# measurement_rev4.net
KiCad netlist of a schematic drawn in Altium Designer
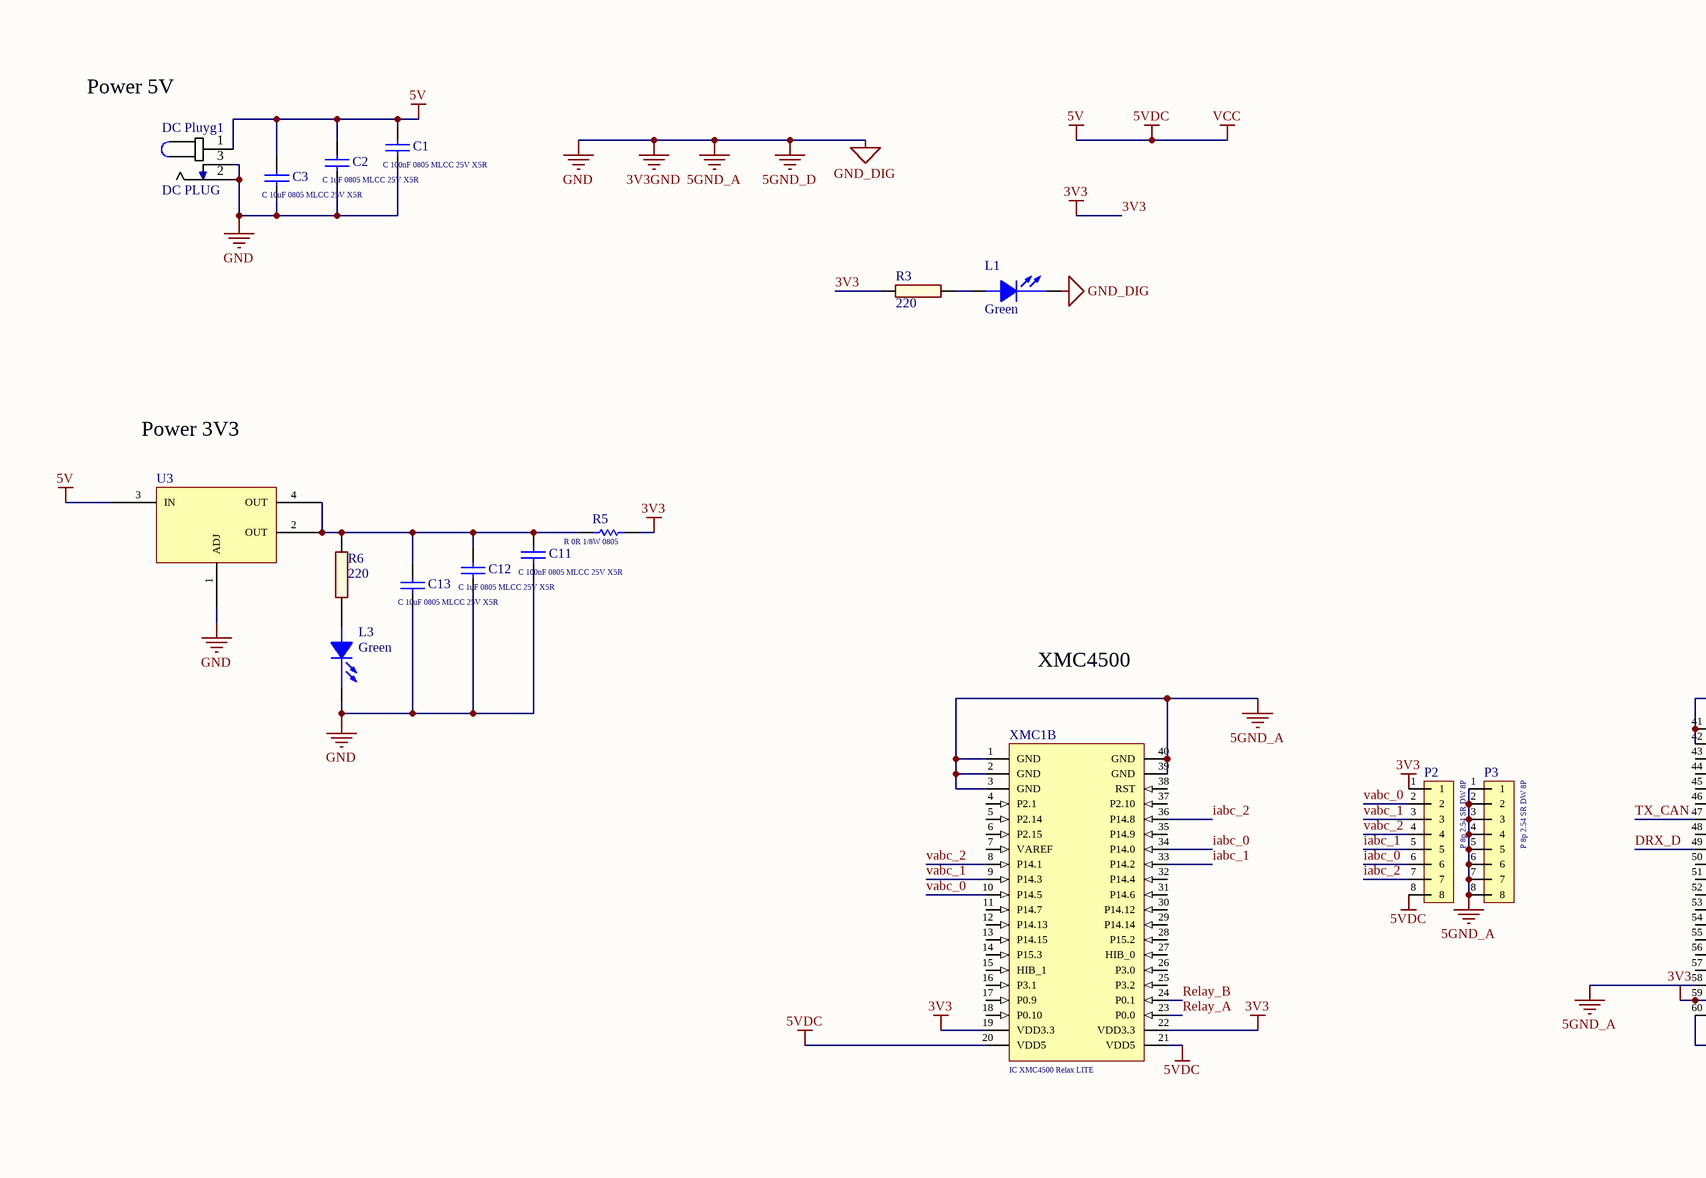
[diagram p0: measurement_rev4.SchDoc, top left]
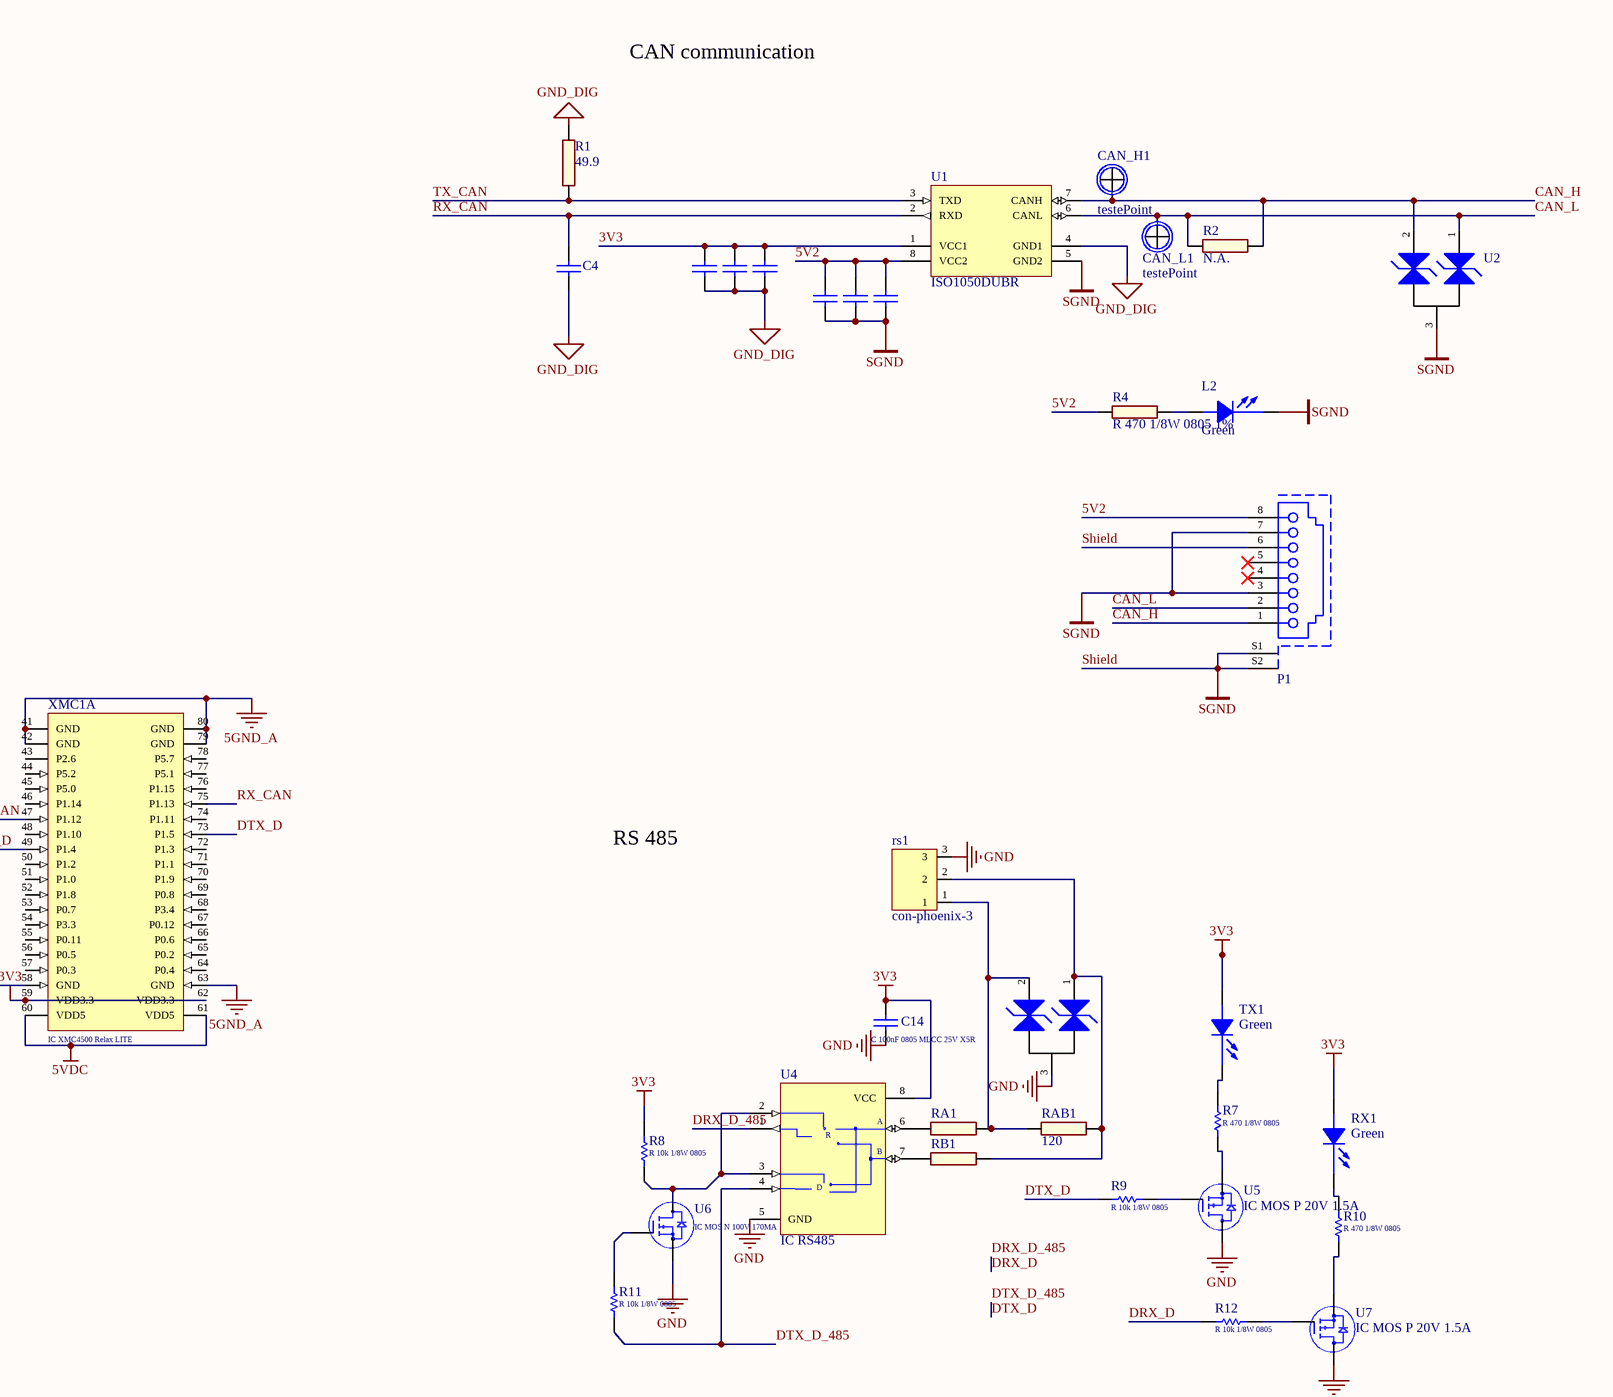
[diagram p1: measurement_rev4.SchDoc, top right]
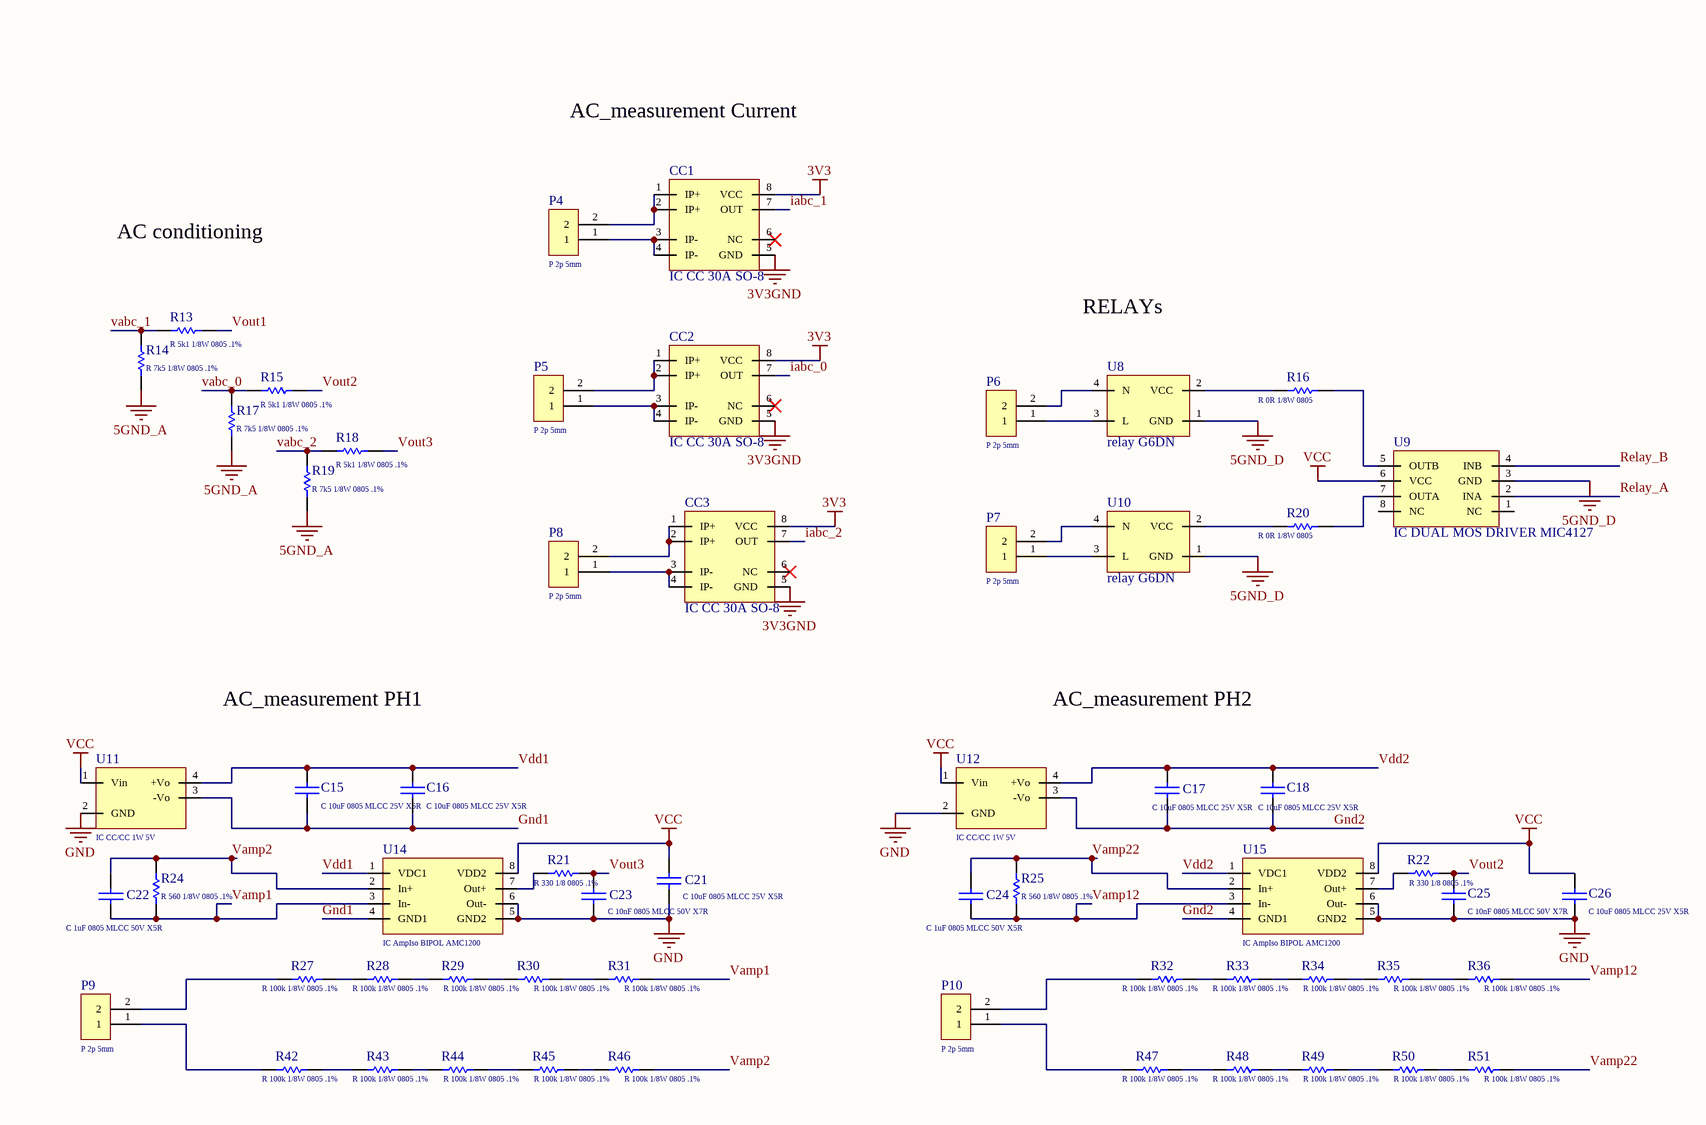
[diagram p2: measurement_rev4.SchDoc, bottom left]
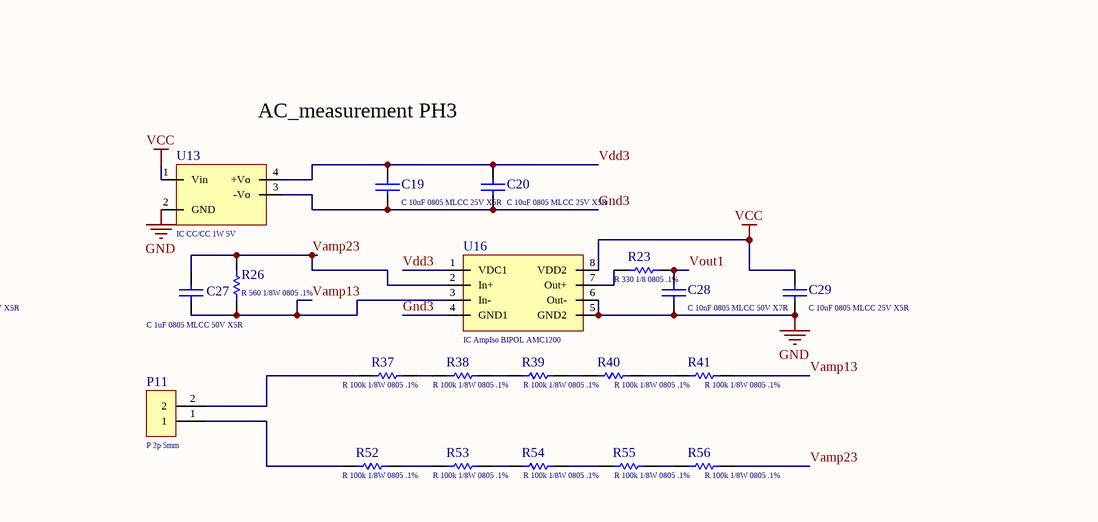
[diagram p3: measurement_rev4.SchDoc, bottom right]

(export (version "E")
  (design (tool "Eeschema 10.0.6"))
  (components
    (comp (ref "C1")
      (value "C 100nF 0805 MLCC 25V X5R")
      (footprint "CAPC_0805")
      (description "MULTILAYER CERAMIC CAPACITORS MLCC - SMD/SMT 100NF 50V 0805 ROHS")
      (fields (field (name "LCSC PART #") "C49678"))
      (libsource (lib "vi_measurement") (part "Capacitor SMD"))
    )
    (comp (ref "C2")
      (value "C 1uF 0805 MLCC 25V X5R")
      (footprint "CAPC_0805")
      (description "MULTILAYER CERAMIC CAPACITORS MLCC - SMD/SMT 1UF 50V 0805 ROHS")
      (fields (field (name "LCSC PART #") "C28323"))
      (libsource (lib "vi_measurement") (part "Capacitor SMD"))
    )
    (comp (ref "C3")
      (value "C 10uF 0805 MLCC 25V X5R")
      (footprint "CAPC_0805")
      (description "Capacitores de cerâmica multicamada MLCC - SMD/SMT 10uF 25V X5R +/-10% 0805 Gen Purp")
      (fields (field (name "LCSC PART #") "C15850"))
      (libsource (lib "vi_measurement") (part "Capacitor SMD"))
    )
    (comp (ref "C4")
      (value "Capacitor")
      (footprint "CAPC_0805")
      (fields (field (name "LCSC PART #") "C1794"))
      (libsource (lib "myLibraryAltium") (part "Capacitor"))
    )
    (comp (ref "C5")
      (value "Capacitor")
      (footprint "CAPC_0805")
      (fields (field (name "LCSC PART #") "C28323"))
      (libsource (lib "myLibraryAltium") (part "Capacitor"))
    )
    (comp (ref "C6")
      (value "Capacitor")
      (footprint "CAPC_0805")
      (fields (field (name "LCSC PART #") "C49678"))
      (libsource (lib "myLibraryAltium") (part "Capacitor"))
    )
    (comp (ref "C7")
      (value "Capacitor")
      (footprint "CAPC_0805")
      (fields (field (name "LCSC PART #") "C1710"))
      (libsource (lib "myLibraryAltium") (part "Capacitor"))
    )
    (comp (ref "C8")
      (value "Capacitor")
      (footprint "CAPC_0805")
      (fields (field (name "LCSC PART #") "C28323"))
      (libsource (lib "myLibraryAltium") (part "Capacitor"))
    )
    (comp (ref "C9")
      (value "Capacitor")
      (footprint "CAPC_0805")
      (fields (field (name "LCSC PART #") "C49678"))
      (libsource (lib "myLibraryAltium") (part "Capacitor"))
    )
    (comp (ref "C10")
      (value "Capacitor")
      (footprint "CAPC_0805")
      (fields (field (name "LCSC PART #") "C1710"))
      (libsource (lib "myLibraryAltium") (part "Capacitor"))
    )
    (comp (ref "C11")
      (value "C 100nF 0805 MLCC 25V X5R")
      (footprint "CAPC_0805")
      (description "MULTILAYER CERAMIC CAPACITORS MLCC - SMD/SMT 100NF 50V 0805 ROHS")
      (fields (field (name "LCSC PART #") "C49678"))
      (libsource (lib "vi_measurement") (part "Capacitor SMD"))
    )
    (comp (ref "C12")
      (value "C 1uF 0805 MLCC 25V X5R")
      (footprint "CAPC_0805")
      (description "MULTILAYER CERAMIC CAPACITORS MLCC - SMD/SMT 1UF 50V 0805 ROHS")
      (fields (field (name "LCSC PART #") "C28323"))
      (libsource (lib "vi_measurement") (part "Capacitor SMD"))
    )
    (comp (ref "C13")
      (value "C 10uF 0805 MLCC 25V X5R")
      (footprint "CAPC_0805")
      (description "Capacitores de cerâmica multicamada MLCC - SMD/SMT 10uF 25V X5R +/-10% 0805 Gen Purp")
      (fields (field (name "LCSC PART #") "C15850"))
      (libsource (lib "vi_measurement") (part "Capacitor SMD"))
    )
    (comp (ref "C14")
      (value "C 100nF 0805 MLCC 25V X5R")
      (footprint "CAPC_0805")
      (description "MULTILAYER CERAMIC CAPACITORS MLCC - SMD/SMT 100NF 50V 0805 ROHS")
      (fields (field (name "LCSC PART #") "C49678"))
      (libsource (lib "vi_measurement") (part "Capacitor SMD"))
    )
    (comp (ref "C15")
      (value "C 10uF 0805 MLCC 25V X5R")
      (footprint "CAPC_0805")
      (description "Capacitores de cerâmica multicamada MLCC - SMD/SMT 10uF 25V X5R +/-10% 0805 Gen Purp")
      (fields (field (name "LCSC PART #") "C15850"))
      (libsource (lib "vi_measurement") (part "Capacitor SMD"))
    )
    (comp (ref "C16")
      (value "C 10uF 0805 MLCC 25V X5R")
      (footprint "CAPC_0805")
      (description "Capacitores de cerâmica multicamada MLCC - SMD/SMT 10uF 25V X5R +/-10% 0805 Gen Purp")
      (fields (field (name "LCSC PART #") "C15850"))
      (libsource (lib "vi_measurement") (part "Capacitor SMD"))
    )
    (comp (ref "C17")
      (value "C 10uF 0805 MLCC 25V X5R")
      (footprint "CAPC_0805")
      (description "Capacitores de cerâmica multicamada MLCC - SMD/SMT 10uF 25V X5R +/-10% 0805 Gen Purp")
      (fields (field (name "LCSC PART #") "C15850"))
      (libsource (lib "vi_measurement") (part "Capacitor SMD"))
    )
    (comp (ref "C18")
      (value "C 10uF 0805 MLCC 25V X5R")
      (footprint "CAPC_0805")
      (description "Capacitores de cerâmica multicamada MLCC - SMD/SMT 10uF 25V X5R +/-10% 0805 Gen Purp")
      (fields (field (name "LCSC PART #") "C15850"))
      (libsource (lib "vi_measurement") (part "Capacitor SMD"))
    )
    (comp (ref "C19")
      (value "C 10uF 0805 MLCC 25V X5R")
      (footprint "CAPC_0805")
      (description "Capacitores de cerâmica multicamada MLCC - SMD/SMT 10uF 25V X5R +/-10% 0805 Gen Purp")
      (fields (field (name "LCSC PART #") "C15850"))
      (libsource (lib "vi_measurement") (part "Capacitor SMD"))
    )
    (comp (ref "C20")
      (value "C 10uF 0805 MLCC 25V X5R")
      (footprint "CAPC_0805")
      (description "Capacitores de cerâmica multicamada MLCC - SMD/SMT 10uF 25V X5R +/-10% 0805 Gen Purp")
      (fields (field (name "LCSC PART #") "C15850"))
      (libsource (lib "vi_measurement") (part "Capacitor SMD"))
    )
    (comp (ref "C21")
      (value "C 10uF 0805 MLCC 25V X5R")
      (footprint "CAPC_0805")
      (description "Capacitores de cerâmica multicamada MLCC - SMD/SMT 10uF 25V X5R +/-10% 0805 Gen Purp")
      (fields (field (name "LCSC PART #") "C15850"))
      (libsource (lib "vi_measurement") (part "Capacitor SMD"))
    )
    (comp (ref "C22")
      (value "C 1uF 0805 MLCC 50V X5R")
      (footprint "CAPC_0805")
      (description "Capacitores de cerâmica multicamada MLCC - SMD/SMT 0805 50V 1uF 20% X5R")
      (fields (field (name "LCSC PART #") "C28323"))
      (libsource (lib "vi_measurement") (part "Capacitor SMD"))
    )
    (comp (ref "C23")
      (value "C 10nF 0805 MLCC 50V X7R")
      (footprint "CAPC_0805")
      (description "Capacitores de cerâmica multicamada MLCC - SMD/SMT 10nF 50V X7R 10%")
      (fields (field (name "LCSC PART #") "C1710"))
      (libsource (lib "vi_measurement") (part "Capacitor SMD"))
    )
    (comp (ref "C24")
      (value "C 1uF 0805 MLCC 50V X5R")
      (footprint "CAPC_0805")
      (description "Capacitores de cerâmica multicamada MLCC - SMD/SMT 0805 50V 1uF 20% X5R")
      (fields (field (name "LCSC PART #") "C28323"))
      (libsource (lib "vi_measurement") (part "Capacitor SMD"))
    )
    (comp (ref "C25")
      (value "C 10nF 0805 MLCC 50V X7R")
      (footprint "CAPC_0805")
      (description "Capacitores de cerâmica multicamada MLCC - SMD/SMT 10nF 50V X7R 10%")
      (fields (field (name "LCSC PART #") "C1710"))
      (libsource (lib "vi_measurement") (part "Capacitor SMD"))
    )
    (comp (ref "C26")
      (value "C 10uF 0805 MLCC 25V X5R")
      (footprint "CAPC_0805")
      (description "Capacitores de cerâmica multicamada MLCC - SMD/SMT 10uF 25V X5R +/-10% 0805 Gen Purp")
      (fields (field (name "LCSC PART #") "C15850"))
      (libsource (lib "vi_measurement") (part "Capacitor SMD"))
    )
    (comp (ref "C27")
      (value "C 1uF 0805 MLCC 50V X5R")
      (footprint "CAPC_0805")
      (description "Capacitores de cerâmica multicamada MLCC - SMD/SMT 0805 50V 1uF 20% X5R")
      (fields (field (name "LCSC PART #") "C28323"))
      (libsource (lib "vi_measurement") (part "Capacitor SMD"))
    )
    (comp (ref "C28")
      (value "C 10nF 0805 MLCC 50V X7R")
      (footprint "CAPC_0805")
      (description "Capacitores de cerâmica multicamada MLCC - SMD/SMT 10nF 50V X7R 10%")
      (fields (field (name "LCSC PART #") "C1710"))
      (libsource (lib "vi_measurement") (part "Capacitor SMD"))
    )
    (comp (ref "C29")
      (value "C 10uF 0805 MLCC 25V X5R")
      (footprint "CAPC_0805")
      (description "Capacitores de cerâmica multicamada MLCC - SMD/SMT 10uF 25V X5R +/-10% 0805 Gen Purp")
      (fields (field (name "LCSC PART #") "C15850"))
      (libsource (lib "vi_measurement") (part "Capacitor SMD"))
    )
    (comp (ref "CAN_H1")
      (value "testePoint")
      (footprint "PAD 2.5MM - FURO 1.25MM")
      (libsource (lib "myLibraryAltium") (part "testePoint"))
    )
    (comp (ref "CAN_L1")
      (value "testePoint")
      (footprint "PAD 2.5MM - FURO 1.25MM")
      (libsource (lib "myLibraryAltium") (part "testePoint"))
    )
    (comp (ref "CC1")
      (value "IC CC 30A SO-8")
      (footprint "CC6303_SOP8")
      (description "Sensores de Corrente de Montagem de Painel Hall Effect IC LF 30A 66 mV/A")
      (fields (field (name "LCSC PART #") "C163283"))
      (libsource (lib "vmorais_libraries") (part "Current_Sensor_cc6303"))
    )
    (comp (ref "CC2")
      (value "IC CC 30A SO-8")
      (footprint "CC6303_SOP8")
      (description "Sensores de Corrente de Montagem de Painel Hall Effect IC LF 30A 66 mV/A")
      (fields (field (name "LCSC PART #") "C163283"))
      (libsource (lib "vmorais_libraries") (part "Current_Sensor_cc6303"))
    )
    (comp (ref "CC3")
      (value "IC CC 30A SO-8")
      (footprint "CC6303_SOP8")
      (description "Sensores de Corrente de Montagem de Painel Hall Effect IC LF 30A 66 mV/A")
      (fields (field (name "LCSC PART #") "C163283"))
      (libsource (lib "vmorais_libraries") (part "Current_Sensor_cc6303"))
    )
    (comp (ref "DC Pluyg1")
      (value "DC PLUG")
      (footprint "DC Plug")
      (libsource (lib "myLibraryAltium") (part "DC PLUG"))
    )
    (comp (ref "L1")
      (value "Green")
      (footprint "CD2012-0805")
      (description "LED 2X1.2MM 570NM GN WTR CLR SMD")
      (fields (field (name "MANUFACTURER") "Kingbright") (field (name "MPN") "APT2012CGCK"))
      (libsource (lib "myLibraryAltium") (part "LED_GREEN"))
    )
    (comp (ref "L2")
      (value "Green")
      (footprint "CD2012-0805")
      (description "LED 2X1.2MM 570NM GN WTR CLR SMD")
      (fields (field (name "MANUFACTURER") "Kingbright") (field (name "MPN") "APT2012CGCK"))
      (libsource (lib "myLibraryAltium") (part "LED_GREEN"))
    )
    (comp (ref "L3")
      (value "Green")
      (footprint "CD2012-0805")
      (description "LED 2X1.2MM 570NM GN WTR CLR SMD")
      (fields (field (name "MANUFACTURER") "Kingbright") (field (name "MPN") "APT2012CGCK"))
      (libsource (lib "myLibraryAltium") (part "LED_GREEN"))
    )
    (comp (ref "P1")
      (value "61500814221")
      (footprint "61500814221")
      (description "Modular Jack Horizontal Shielded 8P8C Tab Down WR-MJ")
      (fields (field (name "PUBLISHER") "Wurth Elektronik"))
      (libsource (lib "Modular Jack Connector_WR-MJ") (part "61500814221"))
    )
    (comp (ref "P2")
      (value "P 8p 2.54 SR DW 8P")
      (footprint "Header 8x1 8.5mm")
      (description "Distribuidores e Alojamento de Fios CGrid Hrd SRDW THo le 8ckt")
      (libsource (lib "vmorais_libraries") (part "jumper_8p"))
    )
    (comp (ref "P3")
      (value "P 8p 2.54 SR DW 8P")
      (footprint "Header 8x1 8.5mm")
      (description "Distribuidores e Alojamento de Fios CGrid Hrd SRDW THo le 8ckt")
      (libsource (lib "vmorais_libraries") (part "jumper_8p"))
    )
    (comp (ref "P4")
      (value "P 2p 5mm")
      (footprint "connector1x2_parafuso")
      (description "Bloques de terminales de PCB de perfil estándar RS de 5,0 mm")
      (libsource (lib "malvega_pcb") (part "gen_purpose_conn_1x2"))
    )
    (comp (ref "P5")
      (value "P 2p 5mm")
      (footprint "connector1x2_parafuso")
      (description "Bloques de terminales de PCB de perfil estándar RS de 5,0 mm")
      (libsource (lib "malvega_pcb") (part "gen_purpose_conn_1x2"))
    )
    (comp (ref "P6")
      (value "P 2p 5mm")
      (footprint "connector1x2_parafuso")
      (description "Bloques de terminales de PCB de perfil estándar RS de 5,0 mm")
      (libsource (lib "malvega_pcb") (part "gen_purpose_conn_1x2"))
    )
    (comp (ref "P7")
      (value "P 2p 5mm")
      (footprint "connector1x2_parafuso")
      (description "Bloques de terminales de PCB de perfil estándar RS de 5,0 mm")
      (libsource (lib "malvega_pcb") (part "gen_purpose_conn_1x2"))
    )
    (comp (ref "P8")
      (value "P 2p 5mm")
      (footprint "connector1x2_parafuso")
      (description "Bloques de terminales de PCB de perfil estándar RS de 5,0 mm")
      (libsource (lib "malvega_pcb") (part "gen_purpose_conn_1x2"))
    )
    (comp (ref "P9")
      (value "P 2p 5mm")
      (footprint "connector1x2_parafuso")
      (description "Bloques de terminales de PCB de perfil estándar RS de 5,0 mm")
      (libsource (lib "malvega_pcb") (part "gen_purpose_conn_1x2"))
    )
    (comp (ref "P10")
      (value "P 2p 5mm")
      (footprint "connector1x2_parafuso")
      (description "Bloques de terminales de PCB de perfil estándar RS de 5,0 mm")
      (libsource (lib "malvega_pcb") (part "gen_purpose_conn_1x2"))
    )
    (comp (ref "P11")
      (value "P 2p 5mm")
      (footprint "connector1x2_parafuso")
      (description "Bloques de terminales de PCB de perfil estándar RS de 5,0 mm")
      (libsource (lib "malvega_pcb") (part "gen_purpose_conn_1x2"))
    )
    (comp (ref "R1")
      (value "49.9")
      (footprint "RESC_0805")
      (description "Thick film resistor, SMD 0402, 1/16W, 1%")
      (fields (field (name "MANUFACTURER") "Generic") (field (name "LCSC PART #") "C17720"))
      (libsource (lib "") (part "R2_1"))
    )
    (comp (ref "R2")
      (value "N.A.")
      (footprint "RESC_0805")
      (description "Thick film resistor, SMD 0402, 1/16W, 1%")
      (fields (field (name "MANUFACTURER") "Generic"))
      (libsource (lib "myLibraryAltium") (part "R2"))
    )
    (comp (ref "R3")
      (value "220")
      (footprint "RESC_0805")
      (description "Thick film resistor, SMD 0402, 1/16W, 1%")
      (fields (field (name "MANUFACTURER") "Generic") (field (name "LCSC PART #") "C17557"))
      (libsource (lib "") (part "R2_2"))
    )
    (comp (ref "R4")
      (value "R 470 1/8W 0805 1%")
      (footprint "RESC_0805")
      (description "Resistores de Filme Espesso - SMD 1/8Watt 470ohms 1% Commercial Use")
      (fields (field (name "MANUFACTURER") "Generic") (field (name "LCSC PART #") "C17710"))
      (libsource (lib "") (part "R2_2"))
    )
    (comp (ref "R5")
      (value "R 0R 1/8W 0805")
      (footprint "RESC_0805")
      (description "Resistores de Filme Fino - SMD 0 ohm")
      (fields (field (name "LCSC PART #") "C17477"))
      (libsource (lib "inversor_50a") (part "Resistor"))
    )
    (comp (ref "R6")
      (value "220")
      (footprint "RESC_0805")
      (description "Thick film resistor, SMD 0402, 1/16W, 1%")
      (fields (field (name "MANUFACTURER") "Generic") (field (name "LCSC PART #") "C17557"))
      (libsource (lib "") (part "R2_1"))
    )
    (comp (ref "R7")
      (value "R 470 1/8W 0805")
      (footprint "RESC_0805")
      (description "CHIP RESISTOR - SURFACE MOUNT 470OHMS ±1% 1/8W 0805 ROHS")
      (fields (field (name "LCSC PART #") "C17710"))
      (libsource (lib "inversor_50a") (part "Resistor"))
    )
    (comp (ref "R8")
      (value "R 10k 1/8W 0805")
      (footprint "RESC_0805")
      (description "CHIP RESISTOR - SURFACE MOUNT 10KOHMS ±1% 1/8W 0805 ROHS")
      (fields (field (name "LCSC PART #") "C17414"))
      (libsource (lib "inversor_50a") (part "Resistor"))
    )
    (comp (ref "R9")
      (value "R 10k 1/8W 0805")
      (footprint "RESC_0805")
      (description "CHIP RESISTOR - SURFACE MOUNT 10KOHMS ±1% 1/8W 0805 ROHS")
      (fields (field (name "LCSC PART #") "C17414"))
      (libsource (lib "inversor_50a") (part "Resistor"))
    )
    (comp (ref "R10")
      (value "R 470 1/8W 0805")
      (footprint "RESC_0805")
      (description "CHIP RESISTOR - SURFACE MOUNT 470OHMS ±1% 1/8W 0805 ROHS")
      (fields (field (name "LCSC PART #") "C17710"))
      (libsource (lib "inversor_50a") (part "Resistor"))
    )
    (comp (ref "R11")
      (value "R 10k 1/8W 0805")
      (footprint "RESC_0805")
      (description "CHIP RESISTOR - SURFACE MOUNT 10KOHMS ±1% 1/8W 0805 ROHS")
      (fields (field (name "LCSC PART #") "C17414"))
      (libsource (lib "inversor_50a") (part "Resistor"))
    )
    (comp (ref "R12")
      (value "R 10k 1/8W 0805")
      (footprint "RESC_0805")
      (description "CHIP RESISTOR - SURFACE MOUNT 10KOHMS ±1% 1/8W 0805 ROHS")
      (fields (field (name "LCSC PART #") "C17414"))
      (libsource (lib "inversor_50a") (part "Resistor"))
    )
    (comp (ref "R13")
      (value "R 5k1 1/8W 0805 .1%")
      (footprint "RESC_0805")
      (description "Resistores de Filme Fino - SMD 0805 5.1Kohm 1/8W .1% 25ppm")
      (fields (field (name "LCSC PART #") "C27834"))
      (libsource (lib "inversor_50a") (part "Resistor"))
    )
    (comp (ref "R14")
      (value "R 7k5 1/8W 0805 .1%")
      (footprint "RESC_0805")
      (description "Resistores de Filme Fino - SMD 7.5K OHM .1% 25ppm")
      (fields (field (name "LCSC PART #") "C17807"))
      (libsource (lib "inversor_50a") (part "Resistor"))
    )
    (comp (ref "R15")
      (value "R 5k1 1/8W 0805 .1%")
      (footprint "RESC_0805")
      (description "Resistores de Filme Fino - SMD 0805 5.1Kohm 1/8W .1% 25ppm")
      (fields (field (name "LCSC PART #") "C27834"))
      (libsource (lib "inversor_50a") (part "Resistor"))
    )
    (comp (ref "R16")
      (value "R 0R 1/8W 0805")
      (footprint "RESC_0805")
      (description "Resistores de Filme Fino - SMD 0 ohm")
      (fields (field (name "LCSC PART #") "C17477"))
      (libsource (lib "inversor_50a") (part "Resistor"))
    )
    (comp (ref "R17")
      (value "R 7k5 1/8W 0805 .1%")
      (footprint "RESC_0805")
      (description "Resistores de Filme Fino - SMD 7.5K OHM .1% 25ppm")
      (fields (field (name "LCSC PART #") "C17807"))
      (libsource (lib "inversor_50a") (part "Resistor"))
    )
    (comp (ref "R18")
      (value "R 5k1 1/8W 0805 .1%")
      (footprint "RESC_0805")
      (description "Resistores de Filme Fino - SMD 0805 5.1Kohm 1/8W .1% 25ppm")
      (fields (field (name "LCSC PART #") "C27834"))
      (libsource (lib "inversor_50a") (part "Resistor"))
    )
    (comp (ref "R19")
      (value "R 7k5 1/8W 0805 .1%")
      (footprint "RESC_0805")
      (description "Resistores de Filme Fino - SMD 7.5K OHM .1% 25ppm")
      (fields (field (name "LCSC PART #") "C17807"))
      (libsource (lib "inversor_50a") (part "Resistor"))
    )
    (comp (ref "R20")
      (value "R 0R 1/8W 0805")
      (footprint "RESC_0805")
      (description "Resistores de Filme Fino - SMD 0 ohm")
      (fields (field (name "LCSC PART #") "C17477"))
      (libsource (lib "inversor_50a") (part "Resistor"))
    )
    (comp (ref "R21")
      (value "R 330 1/8 0805 .1%")
      (footprint "RESC_0805")
      (description "Resistores de Filme Fino - SMD CPF 0805 330R 0.1% 25PPM 1K RL")
      (fields (field (name "LCSC PART #") "C17630"))
      (libsource (lib "inversor_50a") (part "Resistor"))
    )
    (comp (ref "R22")
      (value "R 330 1/8 0805 .1%")
      (footprint "RESC_0805")
      (description "Resistores de Filme Fino - SMD CPF 0805 330R 0.1% 25PPM 1K RL")
      (fields (field (name "LCSC PART #") "C17630"))
      (libsource (lib "inversor_50a") (part "Resistor"))
    )
    (comp (ref "R23")
      (value "R 330 1/8 0805 .1%")
      (footprint "RESC_0805")
      (description "Resistores de Filme Fino - SMD CPF 0805 330R 0.1% 25PPM 1K RL")
      (fields (field (name "LCSC PART #") "C17630"))
      (libsource (lib "inversor_50a") (part "Resistor"))
    )
    (comp (ref "R24")
      (value "R 560 1/8W 0805 .1%")
      (footprint "RESC_0805")
      (description "Resistores de Filme Fino - SMD 1/8W 3.6K ohm .1% 25ppm")
      (fields (field (name "LCSC PART #") "C28636"))
      (libsource (lib "inversor_50a") (part "Resistor"))
    )
    (comp (ref "R25")
      (value "R 560 1/8W 0805 .1%")
      (footprint "RESC_0805")
      (description "Resistores de Filme Fino - SMD 1/8W 3.6K ohm .1% 25ppm")
      (fields (field (name "LCSC PART #") "C28636"))
      (libsource (lib "inversor_50a") (part "Resistor"))
    )
    (comp (ref "R26")
      (value "R 560 1/8W 0805 .1%")
      (footprint "RESC_0805")
      (description "Resistores de Filme Fino - SMD 1/8W 3.6K ohm .1% 25ppm")
      (fields (field (name "LCSC PART #") "C28636"))
      (libsource (lib "inversor_50a") (part "Resistor"))
    )
    (comp (ref "R27")
      (value "R 100k 1/8W 0805 .1%")
      (footprint "RESC_0805")
      (description "Resistores de Filme Fino - SMD 100 Kohm .1% 0805 25PPM")
      (fields (field (name "LCSC PART #") "C17407"))
      (libsource (lib "inversor_50a") (part "Resistor"))
    )
    (comp (ref "R28")
      (value "R 100k 1/8W 0805 .1%")
      (footprint "RESC_0805")
      (description "Resistores de Filme Fino - SMD 100 Kohm .1% 0805 25PPM")
      (fields (field (name "LCSC PART #") "C17407"))
      (libsource (lib "inversor_50a") (part "Resistor"))
    )
    (comp (ref "R29")
      (value "R 100k 1/8W 0805 .1%")
      (footprint "RESC_0805")
      (description "Resistores de Filme Fino - SMD 100 Kohm .1% 0805 25PPM")
      (fields (field (name "LCSC PART #") "C17407"))
      (libsource (lib "inversor_50a") (part "Resistor"))
    )
    (comp (ref "R30")
      (value "R 100k 1/8W 0805 .1%")
      (footprint "RESC_0805")
      (description "Resistores de Filme Fino - SMD 100 Kohm .1% 0805 25PPM")
      (fields (field (name "LCSC PART #") "C17407"))
      (libsource (lib "inversor_50a") (part "Resistor"))
    )
    (comp (ref "R31")
      (value "R 100k 1/8W 0805 .1%")
      (footprint "RESC_0805")
      (description "Resistores de Filme Fino - SMD 100 Kohm .1% 0805 25PPM")
      (fields (field (name "LCSC PART #") "C17407"))
      (libsource (lib "inversor_50a") (part "Resistor"))
    )
    (comp (ref "R32")
      (value "R 100k 1/8W 0805 .1%")
      (footprint "RESC_0805")
      (description "Resistores de Filme Fino - SMD 100 Kohm .1% 0805 25PPM")
      (fields (field (name "LCSC PART #") "C17407"))
      (libsource (lib "inversor_50a") (part "Resistor"))
    )
    (comp (ref "R33")
      (value "R 100k 1/8W 0805 .1%")
      (footprint "RESC_0805")
      (description "Resistores de Filme Fino - SMD 100 Kohm .1% 0805 25PPM")
      (fields (field (name "LCSC PART #") "C17407"))
      (libsource (lib "inversor_50a") (part "Resistor"))
    )
    (comp (ref "R34")
      (value "R 100k 1/8W 0805 .1%")
      (footprint "RESC_0805")
      (description "Resistores de Filme Fino - SMD 100 Kohm .1% 0805 25PPM")
      (fields (field (name "LCSC PART #") "C17407"))
      (libsource (lib "inversor_50a") (part "Resistor"))
    )
    (comp (ref "R35")
      (value "R 100k 1/8W 0805 .1%")
      (footprint "RESC_0805")
      (description "Resistores de Filme Fino - SMD 100 Kohm .1% 0805 25PPM")
      (fields (field (name "LCSC PART #") "C17407"))
      (libsource (lib "inversor_50a") (part "Resistor"))
    )
    (comp (ref "R36")
      (value "R 100k 1/8W 0805 .1%")
      (footprint "RESC_0805")
      (description "Resistores de Filme Fino - SMD 100 Kohm .1% 0805 25PPM")
      (fields (field (name "LCSC PART #") "C17407"))
      (libsource (lib "inversor_50a") (part "Resistor"))
    )
    (comp (ref "R37")
      (value "R 100k 1/8W 0805 .1%")
      (footprint "RESC_0805")
      (description "Resistores de Filme Fino - SMD 100 Kohm .1% 0805 25PPM")
      (fields (field (name "LCSC PART #") "C17407"))
      (libsource (lib "inversor_50a") (part "Resistor"))
    )
    (comp (ref "R38")
      (value "R 100k 1/8W 0805 .1%")
      (footprint "RESC_0805")
      (description "Resistores de Filme Fino - SMD 100 Kohm .1% 0805 25PPM")
      (fields (field (name "LCSC PART #") "C17407"))
      (libsource (lib "inversor_50a") (part "Resistor"))
    )
    (comp (ref "R39")
      (value "R 100k 1/8W 0805 .1%")
      (footprint "RESC_0805")
      (description "Resistores de Filme Fino - SMD 100 Kohm .1% 0805 25PPM")
      (fields (field (name "LCSC PART #") "C17407"))
      (libsource (lib "inversor_50a") (part "Resistor"))
    )
    (comp (ref "R40")
      (value "R 100k 1/8W 0805 .1%")
      (footprint "RESC_0805")
      (description "Resistores de Filme Fino - SMD 100 Kohm .1% 0805 25PPM")
      (fields (field (name "LCSC PART #") "C17407"))
      (libsource (lib "inversor_50a") (part "Resistor"))
    )
    (comp (ref "R41")
      (value "R 100k 1/8W 0805 .1%")
      (footprint "RESC_0805")
      (description "Resistores de Filme Fino - SMD 100 Kohm .1% 0805 25PPM")
      (fields (field (name "LCSC PART #") "C17407"))
      (libsource (lib "inversor_50a") (part "Resistor"))
    )
    (comp (ref "R42")
      (value "R 100k 1/8W 0805 .1%")
      (footprint "RESC_0805")
      (description "Resistores de Filme Fino - SMD 100 Kohm .1% 0805 25PPM")
      (fields (field (name "LCSC PART #") "C17407"))
      (libsource (lib "inversor_50a") (part "Resistor"))
    )
    (comp (ref "R43")
      (value "R 100k 1/8W 0805 .1%")
      (footprint "RESC_0805")
      (description "Resistores de Filme Fino - SMD 100 Kohm .1% 0805 25PPM")
      (fields (field (name "LCSC PART #") "C17407"))
      (libsource (lib "inversor_50a") (part "Resistor"))
    )
    (comp (ref "R44")
      (value "R 100k 1/8W 0805 .1%")
      (footprint "RESC_0805")
      (description "Resistores de Filme Fino - SMD 100 Kohm .1% 0805 25PPM")
      (fields (field (name "LCSC PART #") "C17407"))
      (libsource (lib "inversor_50a") (part "Resistor"))
    )
    (comp (ref "R45")
      (value "R 100k 1/8W 0805 .1%")
      (footprint "RESC_0805")
      (description "Resistores de Filme Fino - SMD 100 Kohm .1% 0805 25PPM")
      (fields (field (name "LCSC PART #") "C17407"))
      (libsource (lib "inversor_50a") (part "Resistor"))
    )
    (comp (ref "R46")
      (value "R 100k 1/8W 0805 .1%")
      (footprint "RESC_0805")
      (description "Resistores de Filme Fino - SMD 100 Kohm .1% 0805 25PPM")
      (fields (field (name "LCSC PART #") "C17407"))
      (libsource (lib "inversor_50a") (part "Resistor"))
    )
    (comp (ref "R47")
      (value "R 100k 1/8W 0805 .1%")
      (footprint "RESC_0805")
      (description "Resistores de Filme Fino - SMD 100 Kohm .1% 0805 25PPM")
      (fields (field (name "LCSC PART #") "C17407"))
      (libsource (lib "inversor_50a") (part "Resistor"))
    )
    (comp (ref "R48")
      (value "R 100k 1/8W 0805 .1%")
      (footprint "RESC_0805")
      (description "Resistores de Filme Fino - SMD 100 Kohm .1% 0805 25PPM")
      (fields (field (name "LCSC PART #") "C17407"))
      (libsource (lib "inversor_50a") (part "Resistor"))
    )
    (comp (ref "R49")
      (value "R 100k 1/8W 0805 .1%")
      (footprint "RESC_0805")
      (description "Resistores de Filme Fino - SMD 100 Kohm .1% 0805 25PPM")
      (fields (field (name "LCSC PART #") "C17407"))
      (libsource (lib "inversor_50a") (part "Resistor"))
    )
    (comp (ref "R50")
      (value "R 100k 1/8W 0805 .1%")
      (footprint "RESC_0805")
      (description "Resistores de Filme Fino - SMD 100 Kohm .1% 0805 25PPM")
      (fields (field (name "LCSC PART #") "C17407"))
      (libsource (lib "inversor_50a") (part "Resistor"))
    )
    (comp (ref "R51")
      (value "R 100k 1/8W 0805 .1%")
      (footprint "RESC_0805")
      (description "Resistores de Filme Fino - SMD 100 Kohm .1% 0805 25PPM")
      (fields (field (name "LCSC PART #") "C17407"))
      (libsource (lib "inversor_50a") (part "Resistor"))
    )
    (comp (ref "R52")
      (value "R 100k 1/8W 0805 .1%")
      (footprint "RESC_0805")
      (description "Resistores de Filme Fino - SMD 100 Kohm .1% 0805 25PPM")
      (fields (field (name "LCSC PART #") "C17407"))
      (libsource (lib "inversor_50a") (part "Resistor"))
    )
    (comp (ref "R53")
      (value "R 100k 1/8W 0805 .1%")
      (footprint "RESC_0805")
      (description "Resistores de Filme Fino - SMD 100 Kohm .1% 0805 25PPM")
      (fields (field (name "LCSC PART #") "C17407"))
      (libsource (lib "inversor_50a") (part "Resistor"))
    )
    (comp (ref "R54")
      (value "R 100k 1/8W 0805 .1%")
      (footprint "RESC_0805")
      (description "Resistores de Filme Fino - SMD 100 Kohm .1% 0805 25PPM")
      (fields (field (name "LCSC PART #") "C17407"))
      (libsource (lib "inversor_50a") (part "Resistor"))
    )
    (comp (ref "R55")
      (value "R 100k 1/8W 0805 .1%")
      (footprint "RESC_0805")
      (description "Resistores de Filme Fino - SMD 100 Kohm .1% 0805 25PPM")
      (fields (field (name "LCSC PART #") "C17407"))
      (libsource (lib "inversor_50a") (part "Resistor"))
    )
    (comp (ref "R56")
      (value "R 100k 1/8W 0805 .1%")
      (footprint "RESC_0805")
      (description "Resistores de Filme Fino - SMD 100 Kohm .1% 0805 25PPM")
      (fields (field (name "LCSC PART #") "C17407"))
      (libsource (lib "inversor_50a") (part "Resistor"))
    )
    (comp (ref "RA1")
      (value "10")
      (footprint "RESC_0805")
      (description "CHIP RESISTOR - SURFACE MOUNT 10OHMS ±1% 1/8W 0805 ROHS")
      (fields (field (name "MANUFACTURER") "Generic") (field (name "LCSC PART #") "C17415"))
      (libsource (lib "myLibraryAltium") (part "R2"))
    )
    (comp (ref "RAB1")
      (value "120")
      (footprint "RESC_1206")
      (description "CHIP RESISTOR - SURFACE MOUNT 120OHMS ±1% 1/4W 1206 ROHS")
      (fields (field (name "MANUFACTURER") "Generic") (field (name "LCSC PART #") "C17909"))
      (libsource (lib "") (part "R2_2"))
    )
    (comp (ref "RB1")
      (value "10")
      (footprint "RESC_0805")
      (description "CHIP RESISTOR - SURFACE MOUNT 10OHMS ±1% 1/8W 0805 ROHS")
      (fields (field (name "MANUFACTURER") "Generic") (field (name "LCSC PART #") "C17415"))
      (libsource (lib "myLibraryAltium") (part "R2"))
    )
    (comp (ref "rs1")
      (value "con-phoenix-3")
      (footprint "molex 3P")
      (libsource (lib "myLibraryAltium") (part "con-phoenix-3"))
    )
    (comp (ref "RX1")
      (value "Green")
      (footprint "CD2012-0805")
      (description "LED 2X1.2MM 570NM GN WTR CLR SMD")
      (fields (field (name "MANUFACTURER") "Kingbright") (field (name "MPN") "APT2012CGCK"))
      (libsource (lib "myLibraryAltium") (part "LED_GREEN"))
    )
    (comp (ref "TVS1")
      (value "Diode_TVS_Array")
      (footprint "SOT23-3")
      (description "DIODES - ESD SOT-23 ROHS")
      (fields (field (name "LCSC PART #") "C404012"))
      (libsource (lib "myLibraryAltium") (part "Diode_TVS_Array"))
    )
    (comp (ref "TX1")
      (value "Green")
      (footprint "CD2012-0805")
      (description "LED 2X1.2MM 570NM GN WTR CLR SMD")
      (fields (field (name "MANUFACTURER") "Kingbright") (field (name "MPN") "APT2012CGCK"))
      (libsource (lib "myLibraryAltium") (part "LED_GREEN"))
    )
    (comp (ref "U1")
      (value "ISO1050DUBR")
      (footprint "DUB8_M")
      (description "Isolated CAN Transceiver, -55 to 105 degC, 8-pin SOP (DUB), Green (RoHS & no Sb/Br)")
      (fields (field (name "LCSC PART #") "C16428"))
      (libsource (lib "myLibraryAltium") (part "ISO1050DUBR"))
    )
    (comp (ref "U2")
      (value "Diode_TVS_Array")
      (footprint "SOT23-3")
      (fields (field (name "LCSC PART #") "C151237"))
      (libsource (lib "myLibraryAltium") (part "Diode_TVS_Array"))
    )
    (comp (ref "U3")
      (value "IC DCDC 3V3 SOT223")
      (footprint "PG-SOT-223")
      (description "LINEAR VOLTAGE REGULATORS SOT-223 ROHS")
      (fields (field (name "LCSC PART #") "C91389"))
      (libsource (lib "V REG LM1117") (part "Component_1"))
    )
    (comp (ref "U4")
      (value "IC RS485")
      (footprint "NSO8_M")
      (description "RS-485 & RS-422 1/1 20MBPS 3V ~ 3.6V SOIC-8_150MIL ROHS")
      (fields (field (name "LCSC PART #") "C57928") (field (name "PUBLISHER") "Altium Limited"))
      (libsource (lib "Maxim Communication Transceiver") (part "MAX481CSA"))
    )
    (comp (ref "U5")
      (value "IC MOS P 20V 1.5A")
      (footprint "SOT23-3")
      (description "MOSFET P TRENCH 20V 1A 2.3V @ 250UA 180 M? @ 1.5A,10V SOT-23(SOT-23-3) ROHS")
      (fields (field (name "LCSC PART #") "C129192"))
      (libsource (lib "myLibraryAltium") (part "MOSFET_P"))
    )
    (comp (ref "U6")
      (value "IC MOS N 100V 170MA")
      (footprint "SOT23-3")
      (description "MOSFET N TRENCH 100V 170MA 2V @ 1MA 6 ? @ 170MA,10V SOT-23(SOT-23-3) ROHS")
      (fields (field (name "LCSC PART #") "C79015"))
      (libsource (lib "myLibraryAltium") (part "MOSFET"))
    )
    (comp (ref "U7")
      (value "IC MOS P 20V 1.5A")
      (footprint "SOT23-3")
      (description "MOSFET P TRENCH 20V 1A 2.3V @ 250UA 180 M? @ 1.5A,10V SOT-23(SOT-23-3) ROHS")
      (fields (field (name "LCSC PART #") "C129192"))
      (libsource (lib "myLibraryAltium") (part "MOSFET_P"))
    )
    (comp (ref "U8")
      (value "relay G6DN")
      (footprint "Relay - G6DN")
      (libsource (lib "vmorais_libraries") (part "Relay - G6DN"))
    )
    (comp (ref "U9")
      (value "IC DUAL MOS DRIVER MIC4127")
      (footprint "SOIC-MIC4126")
      (description "Drivers de portas 1.5A Dual High Speed MOSFET Driver with Low Thermal Impedance")
      (fields (field (name "LCSC PART #") "C20551"))
      (libsource (lib "vmorais_libraries") (part "MOS_DRIVER-MIC4126"))
    )
    (comp (ref "U10")
      (value "relay G6DN")
      (footprint "Relay - G6DN")
      (libsource (lib "vmorais_libraries") (part "Relay - G6DN"))
    )
    (comp (ref "U11")
      (value "IC CC/CC 1W 5V")
      (footprint "DC/DC_ISO")
      (description "Conversores CC/CC com isolação 1W 5Vin 5Vout 200mA SIP7")
      (libsource (lib "vi_measurement") (part "DC/DC_ISO"))
    )
    (comp (ref "U12")
      (value "IC CC/CC 1W 5V")
      (footprint "DC/DC_ISO")
      (description "Conversores CC/CC com isolação 1W 5Vin 5Vout 200mA SIP7")
      (libsource (lib "vi_measurement") (part "DC/DC_ISO"))
    )
    (comp (ref "U13")
      (value "IC CC/CC 1W 5V")
      (footprint "DC/DC_ISO")
      (description "Conversores CC/CC com isolação 1W 5Vin 5Vout 200mA SIP7")
      (libsource (lib "vi_measurement") (part "DC/DC_ISO"))
    )
    (comp (ref "U14")
      (value "IC AmpIso BIPOL AMC1200")
      (footprint "SOIC8")
      (description "Amplificadores de isolamento 4kV peak Iso Amp")
      (fields (field (name "LCSC PART #") "C79905"))
      (libsource (lib "vi_measurement") (part "AMC1200"))
    )
    (comp (ref "U15")
      (value "IC AmpIso BIPOL AMC1200")
      (footprint "SOIC8")
      (description "Amplificadores de isolamento 4kV peak Iso Amp")
      (fields (field (name "LCSC PART #") "C79905"))
      (libsource (lib "vi_measurement") (part "AMC1200"))
    )
    (comp (ref "U16")
      (value "IC AmpIso BIPOL AMC1200")
      (footprint "SOIC8")
      (description "Amplificadores de isolamento 4kV peak Iso Amp")
      (fields (field (name "LCSC PART #") "C79905"))
      (libsource (lib "vi_measurement") (part "AMC1200"))
    )
    (comp (ref "XMC1")
      (value "IC XMC4500 Relax LITE")
      (footprint "XMC4500")
      (libsource (lib "vmorais_libraries") (part "XMC4500"))
    )
  )
  (nets
    (net (code "1") (name "/5V2") (class "Default")
      (node (ref "C10") (pin "2") (pinfunction "2_2") (pintype "passive"))
      (node (ref "C8") (pin "2") (pinfunction "2_2") (pintype "passive"))
      (node (ref "C9") (pin "2") (pinfunction "2_2") (pintype "passive"))
      (node (ref "P1") (pin "8") (pinfunction "8_8") (pintype "passive"))
      (node (ref "R4") (pin "1") (pinfunction "1_1") (pintype "passive"))
      (node (ref "U1") (pin "8") (pinfunction "VCC2_8") (pintype "power_in"))
    )
    (net (code "2") (name "/CAN_H") (class "Default")
      (node (ref "CAN_H1") (pin "1") (pinfunction "1_1") (pintype "passive"))
      (node (ref "P1") (pin "1") (pinfunction "1_1") (pintype "passive"))
      (node (ref "R2") (pin "1") (pinfunction "1_1") (pintype "passive"))
      (node (ref "U1") (pin "7") (pinfunction "CANH_7") (pintype "bidirectional"))
      (node (ref "U2") (pin "2") (pinfunction "2_2") (pintype "passive"))
    )
    (net (code "3") (name "/CAN_L") (class "Default")
      (node (ref "CAN_L1") (pin "1") (pinfunction "1_1") (pintype "passive"))
      (node (ref "P1") (pin "2") (pinfunction "2_2") (pintype "passive"))
      (node (ref "R2") (pin "2") (pinfunction "2_2") (pintype "passive"))
      (node (ref "U1") (pin "6") (pinfunction "CANL_6") (pintype "bidirectional"))
      (node (ref "U2") (pin "1") (pinfunction "1_1") (pintype "passive"))
    )
    (net (code "4") (name "/DRX_D") (class "Default")
      (node (ref "R12") (pin "2") (pinfunction "2_2") (pintype "passive"))
      (node (ref "U4") (pin "1") (pinfunction "RO_1") (pintype "output"))
      (node (ref "XMC1") (pin "49") (pinfunction "P1.4_49") (pintype "input"))
    )
    (net (code "5") (name "/DTX_D") (class "Default")
      (node (ref "R11") (pin "1") (pinfunction "1_1") (pintype "passive"))
      (node (ref "R9") (pin "2") (pinfunction "2_2") (pintype "passive"))
      (node (ref "U4") (pin "4") (pinfunction "DI_4") (pintype "input"))
      (node (ref "XMC1") (pin "73") (pinfunction "P1.5_73") (pintype "input"))
    )
    (net (code "6") (name "/Gnd1") (class "Default")
      (node (ref "C15") (pin "1") (pinfunction "1_1") (pintype "passive"))
      (node (ref "C16") (pin "1") (pinfunction "1_1") (pintype "passive"))
      (node (ref "U11") (pin "3") (pinfunction "-Vo_3") (pintype "passive"))
      (node (ref "U14") (pin "4") (pinfunction "GND1_4") (pintype "passive"))
    )
    (net (code "7") (name "/Gnd2") (class "Default")
      (node (ref "C17") (pin "1") (pinfunction "1_1") (pintype "passive"))
      (node (ref "C18") (pin "1") (pinfunction "1_1") (pintype "passive"))
      (node (ref "U12") (pin "3") (pinfunction "-Vo_3") (pintype "passive"))
      (node (ref "U15") (pin "4") (pinfunction "GND1_4") (pintype "passive"))
    )
    (net (code "8") (name "/Gnd3") (class "Default")
      (node (ref "C19") (pin "1") (pinfunction "1_1") (pintype "passive"))
      (node (ref "C20") (pin "1") (pinfunction "1_1") (pintype "passive"))
      (node (ref "U13") (pin "3") (pinfunction "-Vo_3") (pintype "passive"))
      (node (ref "U16") (pin "4") (pinfunction "GND1_4") (pintype "passive"))
    )
    (net (code "9") (name "/RX_CAN") (class "Default")
      (node (ref "C4") (pin "2") (pinfunction "2_2") (pintype "passive"))
      (node (ref "U1") (pin "2") (pinfunction "RXD_2") (pintype "output"))
      (node (ref "XMC1") (pin "75") (pinfunction "P1.13_75") (pintype "input"))
    )
    (net (code "10") (name "/Relay_A") (class "Default")
      (node (ref "U9") (pin "2") (pinfunction "INA_2") (pintype "passive"))
      (node (ref "XMC1") (pin "23") (pinfunction "P0.0_23") (pintype "input"))
    )
    (net (code "11") (name "/Relay_B") (class "Default")
      (node (ref "U9") (pin "4") (pinfunction "INB_4") (pintype "passive"))
      (node (ref "XMC1") (pin "24") (pinfunction "P0.1_24") (pintype "input"))
    )
    (net (code "12") (name "/TX_CAN") (class "Default")
      (node (ref "R1") (pin "1") (pinfunction "1_1") (pintype "passive"))
      (node (ref "U1") (pin "3") (pinfunction "TXD_3") (pintype "input"))
      (node (ref "XMC1") (pin "47") (pinfunction "P1.12_47") (pintype "input"))
    )
    (net (code "13") (name "/Vamp1") (class "Default")
      (node (ref "C22") (pin "1") (pinfunction "1_1") (pintype "passive"))
      (node (ref "R24") (pin "1") (pinfunction "1_1") (pintype "passive"))
      (node (ref "R31") (pin "2") (pinfunction "2_2") (pintype "passive"))
      (node (ref "U14") (pin "3") (pinfunction "In-_3") (pintype "passive"))
    )
    (net (code "14") (name "/Vamp2") (class "Default")
      (node (ref "C22") (pin "2") (pinfunction "2_2") (pintype "passive"))
      (node (ref "R24") (pin "2") (pinfunction "2_2") (pintype "passive"))
      (node (ref "R46") (pin "2") (pinfunction "2_2") (pintype "passive"))
      (node (ref "U14") (pin "2") (pinfunction "In+_2") (pintype "passive"))
    )
    (net (code "15") (name "/Vamp12") (class "Default")
      (node (ref "C24") (pin "1") (pinfunction "1_1") (pintype "passive"))
      (node (ref "R25") (pin "1") (pinfunction "1_1") (pintype "passive"))
      (node (ref "R36") (pin "2") (pinfunction "2_2") (pintype "passive"))
      (node (ref "U15") (pin "3") (pinfunction "In-_3") (pintype "passive"))
    )
    (net (code "16") (name "/Vamp13") (class "Default")
      (node (ref "C27") (pin "1") (pinfunction "1_1") (pintype "passive"))
      (node (ref "R26") (pin "1") (pinfunction "1_1") (pintype "passive"))
      (node (ref "R41") (pin "2") (pinfunction "2_2") (pintype "passive"))
      (node (ref "U16") (pin "3") (pinfunction "In-_3") (pintype "passive"))
    )
    (net (code "17") (name "/Vamp22") (class "Default")
      (node (ref "C24") (pin "2") (pinfunction "2_2") (pintype "passive"))
      (node (ref "R25") (pin "2") (pinfunction "2_2") (pintype "passive"))
      (node (ref "R51") (pin "2") (pinfunction "2_2") (pintype "passive"))
      (node (ref "U15") (pin "2") (pinfunction "In+_2") (pintype "passive"))
    )
    (net (code "18") (name "/Vamp23") (class "Default")
      (node (ref "C27") (pin "2") (pinfunction "2_2") (pintype "passive"))
      (node (ref "R26") (pin "2") (pinfunction "2_2") (pintype "passive"))
      (node (ref "R56") (pin "2") (pinfunction "2_2") (pintype "passive"))
      (node (ref "U16") (pin "2") (pinfunction "In+_2") (pintype "passive"))
    )
    (net (code "19") (name "/Vdd1") (class "Default")
      (node (ref "C15") (pin "2") (pinfunction "2_2") (pintype "passive"))
      (node (ref "C16") (pin "2") (pinfunction "2_2") (pintype "passive"))
      (node (ref "U11") (pin "4") (pinfunction "+Vo_4") (pintype "passive"))
      (node (ref "U14") (pin "1") (pinfunction "VDC1_1") (pintype "passive"))
    )
    (net (code "20") (name "/Vdd2") (class "Default")
      (node (ref "C17") (pin "2") (pinfunction "2_2") (pintype "passive"))
      (node (ref "C18") (pin "2") (pinfunction "2_2") (pintype "passive"))
      (node (ref "U12") (pin "4") (pinfunction "+Vo_4") (pintype "passive"))
      (node (ref "U15") (pin "1") (pinfunction "VDC1_1") (pintype "passive"))
    )
    (net (code "21") (name "/Vdd3") (class "Default")
      (node (ref "C19") (pin "2") (pinfunction "2_2") (pintype "passive"))
      (node (ref "C20") (pin "2") (pinfunction "2_2") (pintype "passive"))
      (node (ref "U13") (pin "4") (pinfunction "+Vo_4") (pintype "passive"))
      (node (ref "U16") (pin "1") (pinfunction "VDC1_1") (pintype "passive"))
    )
    (net (code "22") (name "/Vout1") (class "Default")
      (node (ref "C28") (pin "2") (pinfunction "2_2") (pintype "passive"))
      (node (ref "R13") (pin "2") (pinfunction "2_2") (pintype "passive"))
      (node (ref "R23") (pin "2") (pinfunction "2_2") (pintype "passive"))
    )
    (net (code "23") (name "/Vout2") (class "Default")
      (node (ref "C25") (pin "2") (pinfunction "2_2") (pintype "passive"))
      (node (ref "R15") (pin "2") (pinfunction "2_2") (pintype "passive"))
      (node (ref "R22") (pin "2") (pinfunction "2_2") (pintype "passive"))
    )
    (net (code "24") (name "/Vout3") (class "Default")
      (node (ref "C23") (pin "2") (pinfunction "2_2") (pintype "passive"))
      (node (ref "R18") (pin "2") (pinfunction "2_2") (pintype "passive"))
      (node (ref "R21") (pin "2") (pinfunction "2_2") (pintype "passive"))
    )
    (net (code "25") (name "/iabc_0") (class "Default")
      (node (ref "CC2") (pin "7") (pinfunction "OUT_7") (pintype "passive"))
      (node (ref "P2") (pin "6") (pinfunction "6_6") (pintype "passive"))
      (node (ref "XMC1") (pin "34") (pinfunction "P14.0_34") (pintype "input"))
    )
    (net (code "26") (name "/iabc_1") (class "Default")
      (node (ref "CC1") (pin "7") (pinfunction "OUT_7") (pintype "passive"))
      (node (ref "P2") (pin "5") (pinfunction "5_5") (pintype "passive"))
      (node (ref "XMC1") (pin "33") (pinfunction "P14.2_33") (pintype "input"))
    )
    (net (code "27") (name "/iabc_2") (class "Default")
      (node (ref "CC3") (pin "7") (pinfunction "OUT_7") (pintype "passive"))
      (node (ref "P2") (pin "7") (pinfunction "7_7") (pintype "passive"))
      (node (ref "XMC1") (pin "36") (pinfunction "P14.8_36") (pintype "input"))
    )
    (net (code "28") (name "/vabc_0") (class "Default")
      (node (ref "P2") (pin "2") (pinfunction "2_2") (pintype "passive"))
      (node (ref "R15") (pin "1") (pinfunction "1_1") (pintype "passive"))
      (node (ref "R17") (pin "2") (pinfunction "2_2") (pintype "passive"))
      (node (ref "XMC1") (pin "10") (pinfunction "P14.5_10") (pintype "input"))
    )
    (net (code "29") (name "/vabc_1") (class "Default")
      (node (ref "P2") (pin "3") (pinfunction "3_3") (pintype "passive"))
      (node (ref "R13") (pin "1") (pinfunction "1_1") (pintype "passive"))
      (node (ref "R14") (pin "2") (pinfunction "2_2") (pintype "passive"))
      (node (ref "XMC1") (pin "9") (pinfunction "P14.3_9") (pintype "input"))
    )
    (net (code "30") (name "/vabc_2") (class "Default")
      (node (ref "P2") (pin "4") (pinfunction "4_4") (pintype "passive"))
      (node (ref "R18") (pin "1") (pinfunction "1_1") (pintype "passive"))
      (node (ref "R19") (pin "2") (pinfunction "2_2") (pintype "passive"))
      (node (ref "XMC1") (pin "8") (pinfunction "P14.1_8") (pintype "input"))
    )
    (net (code "31") (name "3V3") (class "Default")
      (node (ref "C14") (pin "2") (pinfunction "2_2") (pintype "passive"))
      (node (ref "C5") (pin "2") (pinfunction "2_2") (pintype "passive"))
      (node (ref "C6") (pin "2") (pinfunction "2_2") (pintype "passive"))
      (node (ref "C7") (pin "2") (pinfunction "2_2") (pintype "passive"))
      (node (ref "CC1") (pin "8") (pinfunction "VCC_8") (pintype "passive"))
      (node (ref "CC2") (pin "8") (pinfunction "VCC_8") (pintype "passive"))
      (node (ref "CC3") (pin "8") (pinfunction "VCC_8") (pintype "passive"))
      (node (ref "P2") (pin "1") (pinfunction "1_1") (pintype "passive"))
      (node (ref "R3") (pin "1") (pinfunction "1_1") (pintype "passive"))
      (node (ref "R5") (pin "2") (pinfunction "2_2") (pintype "passive"))
      (node (ref "R8") (pin "2") (pinfunction "2_2") (pintype "passive"))
      (node (ref "RX1") (pin "A") (pinfunction "ANODE_A") (pintype "passive"))
      (node (ref "TX1") (pin "A") (pinfunction "ANODE_A") (pintype "passive"))
      (node (ref "U1") (pin "1") (pinfunction "VCC1_1") (pintype "power_in"))
      (node (ref "U4") (pin "8") (pinfunction "VCC_8") (pintype "power_in"))
      (node (ref "XMC1") (pin "19") (pinfunction "VDD3.3_19") (pintype "power_in"))
      (node (ref "XMC1") (pin "22") (pinfunction "VDD3.3_22") (pintype "power_in"))
      (node (ref "XMC1") (pin "59") (pinfunction "VDD3.3_59") (pintype "power_in"))
      (node (ref "XMC1") (pin "62") (pinfunction "VDD3.3_62") (pintype "power_in"))
    )
    (net (code "32") (name "3V3GND") (class "Default")
      (node (ref "C1") (pin "1") (pinfunction "1_1") (pintype "passive"))
      (node (ref "C11") (pin "1") (pinfunction "1_1") (pintype "passive"))
      (node (ref "C12") (pin "1") (pinfunction "1_1") (pintype "passive"))
      (node (ref "C13") (pin "1") (pinfunction "1_1") (pintype "passive"))
      (node (ref "C14") (pin "1") (pinfunction "1_1") (pintype "passive"))
      (node (ref "C2") (pin "1") (pinfunction "1_1") (pintype "passive"))
      (node (ref "C21") (pin "1") (pinfunction "1_1") (pintype "passive"))
      (node (ref "C23") (pin "1") (pinfunction "1_1") (pintype "passive"))
      (node (ref "C25") (pin "1") (pinfunction "1_1") (pintype "passive"))
      (node (ref "C26") (pin "1") (pinfunction "1_1") (pintype "passive"))
      (node (ref "C28") (pin "1") (pinfunction "1_1") (pintype "passive"))
      (node (ref "C29") (pin "1") (pinfunction "1_1") (pintype "passive"))
      (node (ref "C3") (pin "1") (pinfunction "1_1") (pintype "passive"))
      (node (ref "C4") (pin "1") (pinfunction "1_1") (pintype "passive"))
      (node (ref "C5") (pin "1") (pinfunction "1_1") (pintype "passive"))
      (node (ref "C6") (pin "1") (pinfunction "1_1") (pintype "passive"))
      (node (ref "C7") (pin "1") (pinfunction "1_1") (pintype "passive"))
      (node (ref "CC1") (pin "5") (pinfunction "GND_5") (pintype "passive"))
      (node (ref "CC2") (pin "5") (pinfunction "GND_5") (pintype "passive"))
      (node (ref "CC3") (pin "5") (pinfunction "GND_5") (pintype "passive"))
      (node (ref "DC Pluyg1") (pin "2") (pinfunction "2_2") (pintype "passive"))
      (node (ref "DC Pluyg1") (pin "3") (pinfunction "3_3") (pintype "passive"))
      (node (ref "L1") (pin "C") (pinfunction "CATHODE_C") (pintype "passive"))
      (node (ref "L3") (pin "C") (pinfunction "CATHODE_C") (pintype "passive"))
      (node (ref "P3") (pin "1") (pinfunction "1_1") (pintype "passive"))
      (node (ref "P3") (pin "2") (pinfunction "2_2") (pintype "passive"))
      (node (ref "P3") (pin "3") (pinfunction "3_3") (pintype "passive"))
      (node (ref "P3") (pin "4") (pinfunction "4_4") (pintype "passive"))
      (node (ref "P3") (pin "5") (pinfunction "5_5") (pintype "passive"))
      (node (ref "P3") (pin "6") (pinfunction "6_6") (pintype "passive"))
      (node (ref "P3") (pin "7") (pinfunction "7_7") (pintype "passive"))
      (node (ref "P3") (pin "8") (pinfunction "8_8") (pintype "passive"))
      (node (ref "R1") (pin "2") (pinfunction "2_2") (pintype "passive"))
      (node (ref "R14") (pin "1") (pinfunction "1_1") (pintype "passive"))
      (node (ref "R17") (pin "1") (pinfunction "1_1") (pintype "passive"))
      (node (ref "R19") (pin "1") (pinfunction "1_1") (pintype "passive"))
      (node (ref "TVS1") (pin "3") (pinfunction "3_3") (pintype "passive"))
      (node (ref "U1") (pin "4") (pinfunction "GND1_4") (pintype "power_in"))
      (node (ref "U10") (pin "1") (pinfunction "GND_1") (pintype "passive"))
      (node (ref "U11") (pin "2") (pinfunction "GND_2") (pintype "passive"))
      (node (ref "U12") (pin "2") (pinfunction "GND_2") (pintype "passive"))
      (node (ref "U13") (pin "2") (pinfunction "GND_2") (pintype "passive"))
      (node (ref "U14") (pin "5") (pinfunction "GND2_5") (pintype "passive"))
      (node (ref "U14") (pin "6") (pinfunction "Out-_6") (pintype "passive"))
      (node (ref "U15") (pin "5") (pinfunction "GND2_5") (pintype "passive"))
      (node (ref "U15") (pin "6") (pinfunction "Out-_6") (pintype "passive"))
      (node (ref "U16") (pin "5") (pinfunction "GND2_5") (pintype "passive"))
      (node (ref "U16") (pin "6") (pinfunction "Out-_6") (pintype "passive"))
      (node (ref "U3") (pin "1") (pinfunction "ADJ_1") (pintype "passive"))
      (node (ref "U4") (pin "5") (pinfunction "GND_5") (pintype "power_in"))
      (node (ref "U5") (pin "3") (pinfunction "D_3") (pintype "passive"))
      (node (ref "U6") (pin "2") (pinfunction "S_2") (pintype "passive"))
      (node (ref "U7") (pin "3") (pinfunction "D_3") (pintype "passive"))
      (node (ref "U8") (pin "1") (pinfunction "GND_1") (pintype "passive"))
      (node (ref "U9") (pin "3") (pinfunction "GND_3") (pintype "passive"))
      (node (ref "XMC1") (pin "1") (pinfunction "GND_1") (pintype "power_in"))
      (node (ref "XMC1") (pin "2") (pinfunction "GND_2") (pintype "power_in"))
      (node (ref "XMC1") (pin "3") (pinfunction "GND_3") (pintype "power_in"))
      (node (ref "XMC1") (pin "39") (pinfunction "GND_39") (pintype "power_in"))
      (node (ref "XMC1") (pin "40") (pinfunction "GND_40") (pintype "power_in"))
      (node (ref "XMC1") (pin "41") (pinfunction "GND_41") (pintype "power_in"))
      (node (ref "XMC1") (pin "42") (pinfunction "GND_42") (pintype "power_in"))
      (node (ref "XMC1") (pin "58") (pinfunction "GND_58") (pintype "input"))
      (node (ref "XMC1") (pin "63") (pinfunction "GND_63") (pintype "input"))
      (node (ref "XMC1") (pin "79") (pinfunction "GND_79") (pintype "power_in"))
      (node (ref "XMC1") (pin "80") (pinfunction "GND_80") (pintype "power_in"))
      (node (ref "rs1") (pin "3") (pinfunction "3_3") (pintype "passive"))
    )
    (net (code "33") (name "5V") (class "Default")
      (node (ref "C1") (pin "2") (pinfunction "2_2") (pintype "passive"))
      (node (ref "C2") (pin "2") (pinfunction "2_2") (pintype "passive"))
      (node (ref "C21") (pin "2") (pinfunction "2_2") (pintype "passive"))
      (node (ref "C26") (pin "2") (pinfunction "2_2") (pintype "passive"))
      (node (ref "C29") (pin "2") (pinfunction "2_2") (pintype "passive"))
      (node (ref "C3") (pin "2") (pinfunction "2_2") (pintype "passive"))
      (node (ref "DC Pluyg1") (pin "1") (pinfunction "1_1") (pintype "passive"))
      (node (ref "P2") (pin "8") (pinfunction "8_8") (pintype "passive"))
      (node (ref "U11") (pin "1") (pinfunction "Vin_1") (pintype "passive"))
      (node (ref "U12") (pin "1") (pinfunction "Vin_1") (pintype "passive"))
      (node (ref "U13") (pin "1") (pinfunction "Vin_1") (pintype "passive"))
      (node (ref "U14") (pin "8") (pinfunction "VDD2_8") (pintype "passive"))
      (node (ref "U15") (pin "8") (pinfunction "VDD2_8") (pintype "passive"))
      (node (ref "U16") (pin "8") (pinfunction "VDD2_8") (pintype "passive"))
      (node (ref "U3") (pin "3") (pinfunction "IN_3") (pintype "passive"))
      (node (ref "U9") (pin "6") (pinfunction "VCC_6") (pintype "passive"))
      (node (ref "XMC1") (pin "20") (pinfunction "VDD5_20") (pintype "power_in"))
      (node (ref "XMC1") (pin "21") (pinfunction "VDD5_21") (pintype "power_in"))
      (node (ref "XMC1") (pin "60") (pinfunction "VDD5_60") (pintype "power_in"))
      (node (ref "XMC1") (pin "61") (pinfunction "VDD5_61") (pintype "power_in"))
    )
    (net (code "34") (name "Net-(C11-Pad2)") (class "Default")
      (node (ref "C11") (pin "2") (pinfunction "2_2") (pintype "passive"))
      (node (ref "C12") (pin "2") (pinfunction "2_2") (pintype "passive"))
      (node (ref "C13") (pin "2") (pinfunction "2_2") (pintype "passive"))
      (node (ref "R5") (pin "1") (pinfunction "1_1") (pintype "passive"))
      (node (ref "R6") (pin "2") (pinfunction "2_2") (pintype "passive"))
      (node (ref "U3") (pin "2") (pinfunction "OUT_2") (pintype "passive"))
      (node (ref "U3") (pin "4") (pinfunction "OUT_4") (pintype "passive"))
    )
    (net (code "35") (name "Net-(CC1-IP+-Pad1)") (class "Default")
      (node (ref "CC1") (pin "1") (pinfunction "IP+_1") (pintype "passive"))
      (node (ref "CC1") (pin "2") (pinfunction "IP+_2") (pintype "passive"))
      (node (ref "P4") (pin "2") (pinfunction "2_2") (pintype "passive"))
    )
    (net (code "36") (name "Net-(CC1-IP--Pad3)") (class "Default")
      (node (ref "CC1") (pin "3") (pinfunction "IP-_3") (pintype "passive"))
      (node (ref "CC1") (pin "4") (pinfunction "IP-_4") (pintype "passive"))
      (node (ref "P4") (pin "1") (pinfunction "1_1") (pintype "passive"))
    )
    (net (code "37") (name "Net-(CC2-IP+-Pad1)") (class "Default")
      (node (ref "CC2") (pin "1") (pinfunction "IP+_1") (pintype "passive"))
      (node (ref "CC2") (pin "2") (pinfunction "IP+_2") (pintype "passive"))
      (node (ref "P5") (pin "2") (pinfunction "2_2") (pintype "passive"))
    )
    (net (code "38") (name "Net-(CC2-IP--Pad3)") (class "Default")
      (node (ref "CC2") (pin "3") (pinfunction "IP-_3") (pintype "passive"))
      (node (ref "CC2") (pin "4") (pinfunction "IP-_4") (pintype "passive"))
      (node (ref "P5") (pin "1") (pinfunction "1_1") (pintype "passive"))
    )
    (net (code "39") (name "Net-(CC3-IP+-Pad1)") (class "Default")
      (node (ref "CC3") (pin "1") (pinfunction "IP+_1") (pintype "passive"))
      (node (ref "CC3") (pin "2") (pinfunction "IP+_2") (pintype "passive"))
      (node (ref "P8") (pin "2") (pinfunction "2_2") (pintype "passive"))
    )
    (net (code "40") (name "Net-(CC3-IP--Pad3)") (class "Default")
      (node (ref "CC3") (pin "3") (pinfunction "IP-_3") (pintype "passive"))
      (node (ref "CC3") (pin "4") (pinfunction "IP-_4") (pintype "passive"))
      (node (ref "P8") (pin "1") (pinfunction "1_1") (pintype "passive"))
    )
    (net (code "41") (name "Net-(L1-ANODE)") (class "Default")
      (node (ref "L1") (pin "A") (pinfunction "ANODE_A") (pintype "passive"))
      (node (ref "R3") (pin "2") (pinfunction "2_2") (pintype "passive"))
    )
    (net (code "42") (name "Net-(L2-ANODE)") (class "Default")
      (node (ref "L2") (pin "A") (pinfunction "ANODE_A") (pintype "passive"))
      (node (ref "R4") (pin "2") (pinfunction "2_2") (pintype "passive"))
    )
    (net (code "43") (name "Net-(L3-ANODE)") (class "Default")
      (node (ref "L3") (pin "A") (pinfunction "ANODE_A") (pintype "passive"))
      (node (ref "R6") (pin "1") (pinfunction "1_1") (pintype "passive"))
    )
    (net (code "44") (name "Net-(P9-Pad1)") (class "Default")
      (node (ref "P9") (pin "1") (pinfunction "1_1") (pintype "passive"))
      (node (ref "R42") (pin "1") (pinfunction "1_1") (pintype "passive"))
    )
    (net (code "45") (name "Net-(P9-Pad2)") (class "Default")
      (node (ref "P9") (pin "2") (pinfunction "2_2") (pintype "passive"))
      (node (ref "R27") (pin "1") (pinfunction "1_1") (pintype "passive"))
    )
    (net (code "46") (name "Net-(P10-Pad1)") (class "Default")
      (node (ref "P10") (pin "1") (pinfunction "1_1") (pintype "passive"))
      (node (ref "R47") (pin "1") (pinfunction "1_1") (pintype "passive"))
    )
    (net (code "47") (name "Net-(P10-Pad2)") (class "Default")
      (node (ref "P10") (pin "2") (pinfunction "2_2") (pintype "passive"))
      (node (ref "R32") (pin "1") (pinfunction "1_1") (pintype "passive"))
    )
    (net (code "48") (name "Net-(P11-Pad1)") (class "Default")
      (node (ref "P11") (pin "1") (pinfunction "1_1") (pintype "passive"))
      (node (ref "R52") (pin "1") (pinfunction "1_1") (pintype "passive"))
    )
    (net (code "49") (name "Net-(P11-Pad2)") (class "Default")
      (node (ref "P11") (pin "2") (pinfunction "2_2") (pintype "passive"))
      (node (ref "R37") (pin "1") (pinfunction "1_1") (pintype "passive"))
    )
    (net (code "50") (name "Net-(R27-Pad2)") (class "Default")
      (node (ref "R27") (pin "2") (pinfunction "2_2") (pintype "passive"))
      (node (ref "R28") (pin "1") (pinfunction "1_1") (pintype "passive"))
    )
    (net (code "51") (name "Net-(R28-Pad2)") (class "Default")
      (node (ref "R28") (pin "2") (pinfunction "2_2") (pintype "passive"))
      (node (ref "R29") (pin "1") (pinfunction "1_1") (pintype "passive"))
    )
    (net (code "52") (name "Net-(R29-Pad2)") (class "Default")
      (node (ref "R29") (pin "2") (pinfunction "2_2") (pintype "passive"))
      (node (ref "R30") (pin "1") (pinfunction "1_1") (pintype "passive"))
    )
    (net (code "53") (name "Net-(R30-Pad2)") (class "Default")
      (node (ref "R30") (pin "2") (pinfunction "2_2") (pintype "passive"))
      (node (ref "R31") (pin "1") (pinfunction "1_1") (pintype "passive"))
    )
    (net (code "54") (name "Net-(R32-Pad2)") (class "Default")
      (node (ref "R32") (pin "2") (pinfunction "2_2") (pintype "passive"))
      (node (ref "R33") (pin "1") (pinfunction "1_1") (pintype "passive"))
    )
    (net (code "55") (name "Net-(R33-Pad2)") (class "Default")
      (node (ref "R33") (pin "2") (pinfunction "2_2") (pintype "passive"))
      (node (ref "R34") (pin "1") (pinfunction "1_1") (pintype "passive"))
    )
    (net (code "56") (name "Net-(R34-Pad2)") (class "Default")
      (node (ref "R34") (pin "2") (pinfunction "2_2") (pintype "passive"))
      (node (ref "R35") (pin "1") (pinfunction "1_1") (pintype "passive"))
    )
    (net (code "57") (name "Net-(R35-Pad2)") (class "Default")
      (node (ref "R35") (pin "2") (pinfunction "2_2") (pintype "passive"))
      (node (ref "R36") (pin "1") (pinfunction "1_1") (pintype "passive"))
    )
    (net (code "58") (name "Net-(R37-Pad2)") (class "Default")
      (node (ref "R37") (pin "2") (pinfunction "2_2") (pintype "passive"))
      (node (ref "R38") (pin "1") (pinfunction "1_1") (pintype "passive"))
    )
    (net (code "59") (name "Net-(R38-Pad2)") (class "Default")
      (node (ref "R38") (pin "2") (pinfunction "2_2") (pintype "passive"))
      (node (ref "R39") (pin "1") (pinfunction "1_1") (pintype "passive"))
    )
    (net (code "60") (name "Net-(R39-Pad2)") (class "Default")
      (node (ref "R39") (pin "2") (pinfunction "2_2") (pintype "passive"))
      (node (ref "R40") (pin "1") (pinfunction "1_1") (pintype "passive"))
    )
    (net (code "61") (name "Net-(R40-Pad2)") (class "Default")
      (node (ref "R40") (pin "2") (pinfunction "2_2") (pintype "passive"))
      (node (ref "R41") (pin "1") (pinfunction "1_1") (pintype "passive"))
    )
    (net (code "62") (name "Net-(R42-Pad2)") (class "Default")
      (node (ref "R42") (pin "2") (pinfunction "2_2") (pintype "passive"))
      (node (ref "R43") (pin "1") (pinfunction "1_1") (pintype "passive"))
    )
    (net (code "63") (name "Net-(R43-Pad2)") (class "Default")
      (node (ref "R43") (pin "2") (pinfunction "2_2") (pintype "passive"))
      (node (ref "R44") (pin "1") (pinfunction "1_1") (pintype "passive"))
    )
    (net (code "64") (name "Net-(R44-Pad2)") (class "Default")
      (node (ref "R44") (pin "2") (pinfunction "2_2") (pintype "passive"))
      (node (ref "R45") (pin "1") (pinfunction "1_1") (pintype "passive"))
    )
    (net (code "65") (name "Net-(R45-Pad2)") (class "Default")
      (node (ref "R45") (pin "2") (pinfunction "2_2") (pintype "passive"))
      (node (ref "R46") (pin "1") (pinfunction "1_1") (pintype "passive"))
    )
    (net (code "66") (name "Net-(R47-Pad2)") (class "Default")
      (node (ref "R47") (pin "2") (pinfunction "2_2") (pintype "passive"))
      (node (ref "R48") (pin "1") (pinfunction "1_1") (pintype "passive"))
    )
    (net (code "67") (name "Net-(R48-Pad2)") (class "Default")
      (node (ref "R48") (pin "2") (pinfunction "2_2") (pintype "passive"))
      (node (ref "R49") (pin "1") (pinfunction "1_1") (pintype "passive"))
    )
    (net (code "68") (name "Net-(R49-Pad2)") (class "Default")
      (node (ref "R49") (pin "2") (pinfunction "2_2") (pintype "passive"))
      (node (ref "R50") (pin "1") (pinfunction "1_1") (pintype "passive"))
    )
    (net (code "69") (name "Net-(R50-Pad2)") (class "Default")
      (node (ref "R50") (pin "2") (pinfunction "2_2") (pintype "passive"))
      (node (ref "R51") (pin "1") (pinfunction "1_1") (pintype "passive"))
    )
    (net (code "70") (name "Net-(R52-Pad2)") (class "Default")
      (node (ref "R52") (pin "2") (pinfunction "2_2") (pintype "passive"))
      (node (ref "R53") (pin "1") (pinfunction "1_1") (pintype "passive"))
    )
    (net (code "71") (name "Net-(R53-Pad2)") (class "Default")
      (node (ref "R53") (pin "2") (pinfunction "2_2") (pintype "passive"))
      (node (ref "R54") (pin "1") (pinfunction "1_1") (pintype "passive"))
    )
    (net (code "72") (name "Net-(R54-Pad2)") (class "Default")
      (node (ref "R54") (pin "2") (pinfunction "2_2") (pintype "passive"))
      (node (ref "R55") (pin "1") (pinfunction "1_1") (pintype "passive"))
    )
    (net (code "73") (name "Net-(R55-Pad2)") (class "Default")
      (node (ref "R55") (pin "2") (pinfunction "2_2") (pintype "passive"))
      (node (ref "R56") (pin "1") (pinfunction "1_1") (pintype "passive"))
    )
    (net (code "74") (name "Net-(RA1-Pad1)") (class "Default")
      (node (ref "RA1") (pin "1") (pinfunction "1_1") (pintype "passive"))
      (node (ref "RAB1") (pin "1") (pinfunction "1_1") (pintype "passive"))
      (node (ref "TVS1") (pin "2") (pinfunction "2_2") (pintype "passive"))
      (node (ref "rs1") (pin "1") (pinfunction "1_1") (pintype "passive"))
    )
    (net (code "75") (name "Net-(RAB1-Pad2)") (class "Default")
      (node (ref "RAB1") (pin "2") (pinfunction "2_2") (pintype "passive"))
      (node (ref "RB1") (pin "1") (pinfunction "1_1") (pintype "passive"))
      (node (ref "TVS1") (pin "1") (pinfunction "1_1") (pintype "passive"))
      (node (ref "rs1") (pin "2") (pinfunction "2_2") (pintype "passive"))
    )
    (net (code "76") (name "Net-(RX1-CATHODE)") (class "Default")
      (node (ref "R10") (pin "1") (pinfunction "1_1") (pintype "passive"))
      (node (ref "RX1") (pin "C") (pinfunction "CATHODE_C") (pintype "passive"))
    )
    (net (code "77") (name "Net-(TX1-CATHODE)") (class "Default")
      (node (ref "R7") (pin "1") (pinfunction "1_1") (pintype "passive"))
      (node (ref "TX1") (pin "C") (pinfunction "CATHODE_C") (pintype "passive"))
    )
    (net (code "78") (name "Net-(U4-A)") (class "Default")
      (node (ref "RA1") (pin "2") (pinfunction "2_2") (pintype "passive"))
      (node (ref "U4") (pin "6") (pinfunction "A_6") (pintype "bidirectional"))
    )
    (net (code "79") (name "Net-(U4-B)") (class "Default")
      (node (ref "RB1") (pin "2") (pinfunction "2_2") (pintype "passive"))
      (node (ref "U4") (pin "7") (pinfunction "B_7") (pintype "bidirectional"))
    )
    (net (code "80") (name "Net-(U4-DE)") (class "Default")
      (node (ref "R8") (pin "1") (pinfunction "1_1") (pintype "passive"))
      (node (ref "U4") (pin "2") (pinfunction "~{RE}_2") (pintype "input"))
      (node (ref "U4") (pin "3") (pinfunction "DE_3") (pintype "input"))
      (node (ref "U6") (pin "3") (pinfunction "D_3") (pintype "passive"))
    )
    (net (code "81") (name "Net-(U5-G)") (class "Default")
      (node (ref "R9") (pin "1") (pinfunction "1_1") (pintype "passive"))
      (node (ref "U5") (pin "1") (pinfunction "G_1") (pintype "passive"))
    )
    (net (code "82") (name "Net-(U5-S)") (class "Default")
      (node (ref "R7") (pin "2") (pinfunction "2_2") (pintype "passive"))
      (node (ref "U5") (pin "2") (pinfunction "S_2") (pintype "passive"))
    )
    (net (code "83") (name "Net-(U6-G)") (class "Default")
      (node (ref "R11") (pin "2") (pinfunction "2_2") (pintype "passive"))
      (node (ref "U6") (pin "1") (pinfunction "G_1") (pintype "passive"))
    )
    (net (code "84") (name "Net-(U7-G)") (class "Default")
      (node (ref "R12") (pin "1") (pinfunction "1_1") (pintype "passive"))
      (node (ref "U7") (pin "1") (pinfunction "G_1") (pintype "passive"))
    )
    (net (code "85") (name "Net-(U7-S)") (class "Default")
      (node (ref "R10") (pin "2") (pinfunction "2_2") (pintype "passive"))
      (node (ref "U7") (pin "2") (pinfunction "S_2") (pintype "passive"))
    )
    (net (code "86") (name "Net-(U8-L)") (class "Default")
      (node (ref "P6") (pin "1") (pinfunction "1_1") (pintype "passive"))
      (node (ref "U8") (pin "3") (pinfunction "L_3") (pintype "passive"))
    )
    (net (code "87") (name "Net-(U8-N)") (class "Default")
      (node (ref "P6") (pin "2") (pinfunction "2_2") (pintype "passive"))
      (node (ref "U8") (pin "4") (pinfunction "N_4") (pintype "passive"))
    )
    (net (code "88") (name "Net-(U8-VCC)") (class "Default")
      (node (ref "R16") (pin "1") (pinfunction "1_1") (pintype "passive"))
      (node (ref "U8") (pin "2") (pinfunction "VCC_2") (pintype "passive"))
    )
    (net (code "89") (name "Net-(U9-OUTA)") (class "Default")
      (node (ref "R20") (pin "2") (pinfunction "2_2") (pintype "passive"))
      (node (ref "U9") (pin "7") (pinfunction "OUTA_7") (pintype "passive"))
    )
    (net (code "90") (name "Net-(U9-OUTB)") (class "Default")
      (node (ref "R16") (pin "2") (pinfunction "2_2") (pintype "passive"))
      (node (ref "U9") (pin "5") (pinfunction "OUTB_5") (pintype "passive"))
    )
    (net (code "91") (name "Net-(U10-L)") (class "Default")
      (node (ref "P7") (pin "1") (pinfunction "1_1") (pintype "passive"))
      (node (ref "U10") (pin "3") (pinfunction "L_3") (pintype "passive"))
    )
    (net (code "92") (name "Net-(U10-N)") (class "Default")
      (node (ref "P7") (pin "2") (pinfunction "2_2") (pintype "passive"))
      (node (ref "U10") (pin "4") (pinfunction "N_4") (pintype "passive"))
    )
    (net (code "93") (name "Net-(U10-VCC)") (class "Default")
      (node (ref "R20") (pin "1") (pinfunction "1_1") (pintype "passive"))
      (node (ref "U10") (pin "2") (pinfunction "VCC_2") (pintype "passive"))
    )
    (net (code "94") (name "Net-(U14-Out+)") (class "Default")
      (node (ref "R21") (pin "1") (pinfunction "1_1") (pintype "passive"))
      (node (ref "U14") (pin "7") (pinfunction "Out+_7") (pintype "passive"))
    )
    (net (code "95") (name "Net-(U15-Out+)") (class "Default")
      (node (ref "R22") (pin "1") (pinfunction "1_1") (pintype "passive"))
      (node (ref "U15") (pin "7") (pinfunction "Out+_7") (pintype "passive"))
    )
    (net (code "96") (name "Net-(U16-Out+)") (class "Default")
      (node (ref "R23") (pin "1") (pinfunction "1_1") (pintype "passive"))
      (node (ref "U16") (pin "7") (pinfunction "Out+_7") (pintype "passive"))
    )
    (net (code "97") (name "SGND") (class "Default")
      (node (ref "C10") (pin "1") (pinfunction "1_1") (pintype "passive"))
      (node (ref "C8") (pin "1") (pinfunction "1_1") (pintype "passive"))
      (node (ref "C9") (pin "1") (pinfunction "1_1") (pintype "passive"))
      (node (ref "L2") (pin "C") (pinfunction "CATHODE_C") (pintype "passive"))
      (node (ref "P1") (pin "3") (pinfunction "3_3") (pintype "passive"))
      (node (ref "P1") (pin "6") (pinfunction "6_6") (pintype "passive"))
      (node (ref "P1") (pin "7") (pinfunction "7_7") (pintype "passive"))
      (node (ref "P1") (pin "S1") (pinfunction "Shield_S1") (pintype "passive"))
      (node (ref "P1") (pin "S2") (pinfunction "Shield_S2") (pintype "passive"))
      (node (ref "U1") (pin "5") (pinfunction "GND2_5") (pintype "power_in"))
      (node (ref "U2") (pin "3") (pinfunction "3_3") (pintype "passive"))
    )
    (net (code "98") (name "unconnected-(CC1-NC-Pad6)") (class "Default")
      (node (ref "CC1") (pin "6") (pinfunction "NC_6") (pintype "passive+no_connect"))
    )
    (net (code "99") (name "unconnected-(CC2-NC-Pad6)") (class "Default")
      (node (ref "CC2") (pin "6") (pinfunction "NC_6") (pintype "passive+no_connect"))
    )
    (net (code "100") (name "unconnected-(CC3-NC-Pad6)") (class "Default")
      (node (ref "CC3") (pin "6") (pinfunction "NC_6") (pintype "passive+no_connect"))
    )
    (net (code "101") (name "unconnected-(P1-Pad4)") (class "Default")
      (node (ref "P1") (pin "4") (pinfunction "4_4") (pintype "passive+no_connect"))
    )
    (net (code "102") (name "unconnected-(P1-Pad5)") (class "Default")
      (node (ref "P1") (pin "5") (pinfunction "5_5") (pintype "passive+no_connect"))
    )
    (net (code "103") (name "unconnected-(U9-NC-Pad1)") (class "Default")
      (node (ref "U9") (pin "1") (pinfunction "NC_1") (pintype "passive"))
    )
    (net (code "104") (name "unconnected-(U9-NC-Pad8)") (class "Default")
      (node (ref "U9") (pin "8") (pinfunction "NC_8") (pintype "passive"))
    )
    (net (code "105") (name "unconnected-(XMC1A-P0.2-Pad65)") (class "Default")
      (node (ref "XMC1") (pin "65") (pinfunction "P0.2_65") (pintype "input"))
    )
    (net (code "106") (name "unconnected-(XMC1A-P0.3-Pad57)") (class "Default")
      (node (ref "XMC1") (pin "57") (pinfunction "P0.3_57") (pintype "input"))
    )
    (net (code "107") (name "unconnected-(XMC1A-P0.4-Pad64)") (class "Default")
      (node (ref "XMC1") (pin "64") (pinfunction "P0.4_64") (pintype "input"))
    )
    (net (code "108") (name "unconnected-(XMC1A-P0.5-Pad56)") (class "Default")
      (node (ref "XMC1") (pin "56") (pinfunction "P0.5_56") (pintype "input"))
    )
    (net (code "109") (name "unconnected-(XMC1A-P0.6-Pad66)") (class "Default")
      (node (ref "XMC1") (pin "66") (pinfunction "P0.6_66") (pintype "input"))
    )
    (net (code "110") (name "unconnected-(XMC1A-P0.7-Pad53)") (class "Default")
      (node (ref "XMC1") (pin "53") (pinfunction "P0.7_53") (pintype "input"))
    )
    (net (code "111") (name "unconnected-(XMC1A-P0.8-Pad69)") (class "Default")
      (node (ref "XMC1") (pin "69") (pinfunction "P0.8_69") (pintype "input"))
    )
    (net (code "112") (name "unconnected-(XMC1A-P0.11-Pad55)") (class "Default")
      (node (ref "XMC1") (pin "55") (pinfunction "P0.11_55") (pintype "input"))
    )
    (net (code "113") (name "unconnected-(XMC1A-P0.12-Pad67)") (class "Default")
      (node (ref "XMC1") (pin "67") (pinfunction "P0.12_67") (pintype "input"))
    )
    (net (code "114") (name "unconnected-(XMC1A-P1.0-Pad51)") (class "Default")
      (node (ref "XMC1") (pin "51") (pinfunction "P1.0_51") (pintype "input"))
    )
    (net (code "115") (name "unconnected-(XMC1A-P1.1-Pad71)") (class "Default")
      (node (ref "XMC1") (pin "71") (pinfunction "P1.1_71") (pintype "input"))
    )
    (net (code "116") (name "unconnected-(XMC1A-P1.2-Pad50)") (class "Default")
      (node (ref "XMC1") (pin "50") (pinfunction "P1.2_50") (pintype "input"))
    )
    (net (code "117") (name "unconnected-(XMC1A-P1.3-Pad72)") (class "Default")
      (node (ref "XMC1") (pin "72") (pinfunction "P1.3_72") (pintype "input"))
    )
    (net (code "118") (name "unconnected-(XMC1A-P1.8-Pad52)") (class "Default")
      (node (ref "XMC1") (pin "52") (pinfunction "P1.8_52") (pintype "input"))
    )
    (net (code "119") (name "unconnected-(XMC1A-P1.9-Pad70)") (class "Default")
      (node (ref "XMC1") (pin "70") (pinfunction "P1.9_70") (pintype "input"))
    )
    (net (code "120") (name "unconnected-(XMC1A-P1.10-Pad48)") (class "Default")
      (node (ref "XMC1") (pin "48") (pinfunction "P1.10_48") (pintype "input"))
    )
    (net (code "121") (name "unconnected-(XMC1A-P1.11-Pad74)") (class "Default")
      (node (ref "XMC1") (pin "74") (pinfunction "P1.11_74") (pintype "input"))
    )
    (net (code "122") (name "unconnected-(XMC1A-P1.14-Pad46)") (class "Default")
      (node (ref "XMC1") (pin "46") (pinfunction "P1.14_46") (pintype "input"))
    )
    (net (code "123") (name "unconnected-(XMC1A-P1.15-Pad76)") (class "Default")
      (node (ref "XMC1") (pin "76") (pinfunction "P1.15_76") (pintype "input"))
    )
    (net (code "124") (name "unconnected-(XMC1A-P2.6-Pad43)") (class "Default")
      (node (ref "XMC1") (pin "43") (pinfunction "P2.6_43") (pintype "power_in"))
    )
    (net (code "125") (name "unconnected-(XMC1A-P3.3-Pad54)") (class "Default")
      (node (ref "XMC1") (pin "54") (pinfunction "P3.3_54") (pintype "input"))
    )
    (net (code "126") (name "unconnected-(XMC1A-P3.4-Pad68)") (class "Default")
      (node (ref "XMC1") (pin "68") (pinfunction "P3.4_68") (pintype "input"))
    )
    (net (code "127") (name "unconnected-(XMC1A-P5.0-Pad45)") (class "Default")
      (node (ref "XMC1") (pin "45") (pinfunction "P5.0_45") (pintype "input"))
    )
    (net (code "128") (name "unconnected-(XMC1A-P5.1-Pad77)") (class "Default")
      (node (ref "XMC1") (pin "77") (pinfunction "P5.1_77") (pintype "input"))
    )
    (net (code "129") (name "unconnected-(XMC1A-P5.2-Pad44)") (class "Default")
      (node (ref "XMC1") (pin "44") (pinfunction "P5.2_44") (pintype "input"))
    )
    (net (code "130") (name "unconnected-(XMC1A-P5.7-Pad78)") (class "Default")
      (node (ref "XMC1") (pin "78") (pinfunction "P5.7_78") (pintype "input"))
    )
    (net (code "131") (name "unconnected-(XMC1B-HIB_0-Pad27)") (class "Default")
      (node (ref "XMC1") (pin "27") (pinfunction "HIB_0_27") (pintype "input"))
    )
    (net (code "132") (name "unconnected-(XMC1B-HIB_1-Pad15)") (class "Default")
      (node (ref "XMC1") (pin "15") (pinfunction "HIB_1_15") (pintype "input"))
    )
    (net (code "133") (name "unconnected-(XMC1B-P0.9-Pad17)") (class "Default")
      (node (ref "XMC1") (pin "17") (pinfunction "P0.9_17") (pintype "input"))
    )
    (net (code "134") (name "unconnected-(XMC1B-P0.10-Pad18)") (class "Default")
      (node (ref "XMC1") (pin "18") (pinfunction "P0.10_18") (pintype "input"))
    )
    (net (code "135") (name "unconnected-(XMC1B-P2.1-Pad4)") (class "Default")
      (node (ref "XMC1") (pin "4") (pinfunction "P2.1_4") (pintype "input"))
    )
    (net (code "136") (name "unconnected-(XMC1B-P2.10-Pad37)") (class "Default")
      (node (ref "XMC1") (pin "37") (pinfunction "P2.10_37") (pintype "input"))
    )
    (net (code "137") (name "unconnected-(XMC1B-P2.14-Pad5)") (class "Default")
      (node (ref "XMC1") (pin "5") (pinfunction "P2.14_5") (pintype "input"))
    )
    (net (code "138") (name "unconnected-(XMC1B-P2.15-Pad6)") (class "Default")
      (node (ref "XMC1") (pin "6") (pinfunction "P2.15_6") (pintype "input"))
    )
    (net (code "139") (name "unconnected-(XMC1B-P3.0-Pad26)") (class "Default")
      (node (ref "XMC1") (pin "26") (pinfunction "P3.0_26") (pintype "input"))
    )
    (net (code "140") (name "unconnected-(XMC1B-P3.1-Pad16)") (class "Default")
      (node (ref "XMC1") (pin "16") (pinfunction "P3.1_16") (pintype "input"))
    )
    (net (code "141") (name "unconnected-(XMC1B-P3.2-Pad25)") (class "Default")
      (node (ref "XMC1") (pin "25") (pinfunction "P3.2_25") (pintype "input"))
    )
    (net (code "142") (name "unconnected-(XMC1B-P14.4-Pad32)") (class "Default")
      (node (ref "XMC1") (pin "32") (pinfunction "P14.4_32") (pintype "input"))
    )
    (net (code "143") (name "unconnected-(XMC1B-P14.6-Pad31)") (class "Default")
      (node (ref "XMC1") (pin "31") (pinfunction "P14.6_31") (pintype "input"))
    )
    (net (code "144") (name "unconnected-(XMC1B-P14.7-Pad11)") (class "Default")
      (node (ref "XMC1") (pin "11") (pinfunction "P14.7_11") (pintype "input"))
    )
    (net (code "145") (name "unconnected-(XMC1B-P14.9-Pad35)") (class "Default")
      (node (ref "XMC1") (pin "35") (pinfunction "P14.9_35") (pintype "input"))
    )
    (net (code "146") (name "unconnected-(XMC1B-P14.12-Pad30)") (class "Default")
      (node (ref "XMC1") (pin "30") (pinfunction "P14.12_30") (pintype "input"))
    )
    (net (code "147") (name "unconnected-(XMC1B-P14.13-Pad12)") (class "Default")
      (node (ref "XMC1") (pin "12") (pinfunction "P14.13_12") (pintype "input"))
    )
    (net (code "148") (name "unconnected-(XMC1B-P14.14-Pad29)") (class "Default")
      (node (ref "XMC1") (pin "29") (pinfunction "P14.14_29") (pintype "input"))
    )
    (net (code "149") (name "unconnected-(XMC1B-P14.15-Pad13)") (class "Default")
      (node (ref "XMC1") (pin "13") (pinfunction "P14.15_13") (pintype "input"))
    )
    (net (code "150") (name "unconnected-(XMC1B-P15.2-Pad28)") (class "Default")
      (node (ref "XMC1") (pin "28") (pinfunction "P15.2_28") (pintype "input"))
    )
    (net (code "151") (name "unconnected-(XMC1B-P15.3-Pad14)") (class "Default")
      (node (ref "XMC1") (pin "14") (pinfunction "P15.3_14") (pintype "input"))
    )
    (net (code "152") (name "unconnected-(XMC1B-RST-Pad38)") (class "Default")
      (node (ref "XMC1") (pin "38") (pinfunction "RST_38") (pintype "input"))
    )
    (net (code "153") (name "unconnected-(XMC1B-VAREF-Pad7)") (class "Default")
      (node (ref "XMC1") (pin "7") (pinfunction "VAREF_7") (pintype "input"))
    )
  )
)
